# 17_USB_3_0.net
KiCad netlist of a schematic drawn in Altium Designer
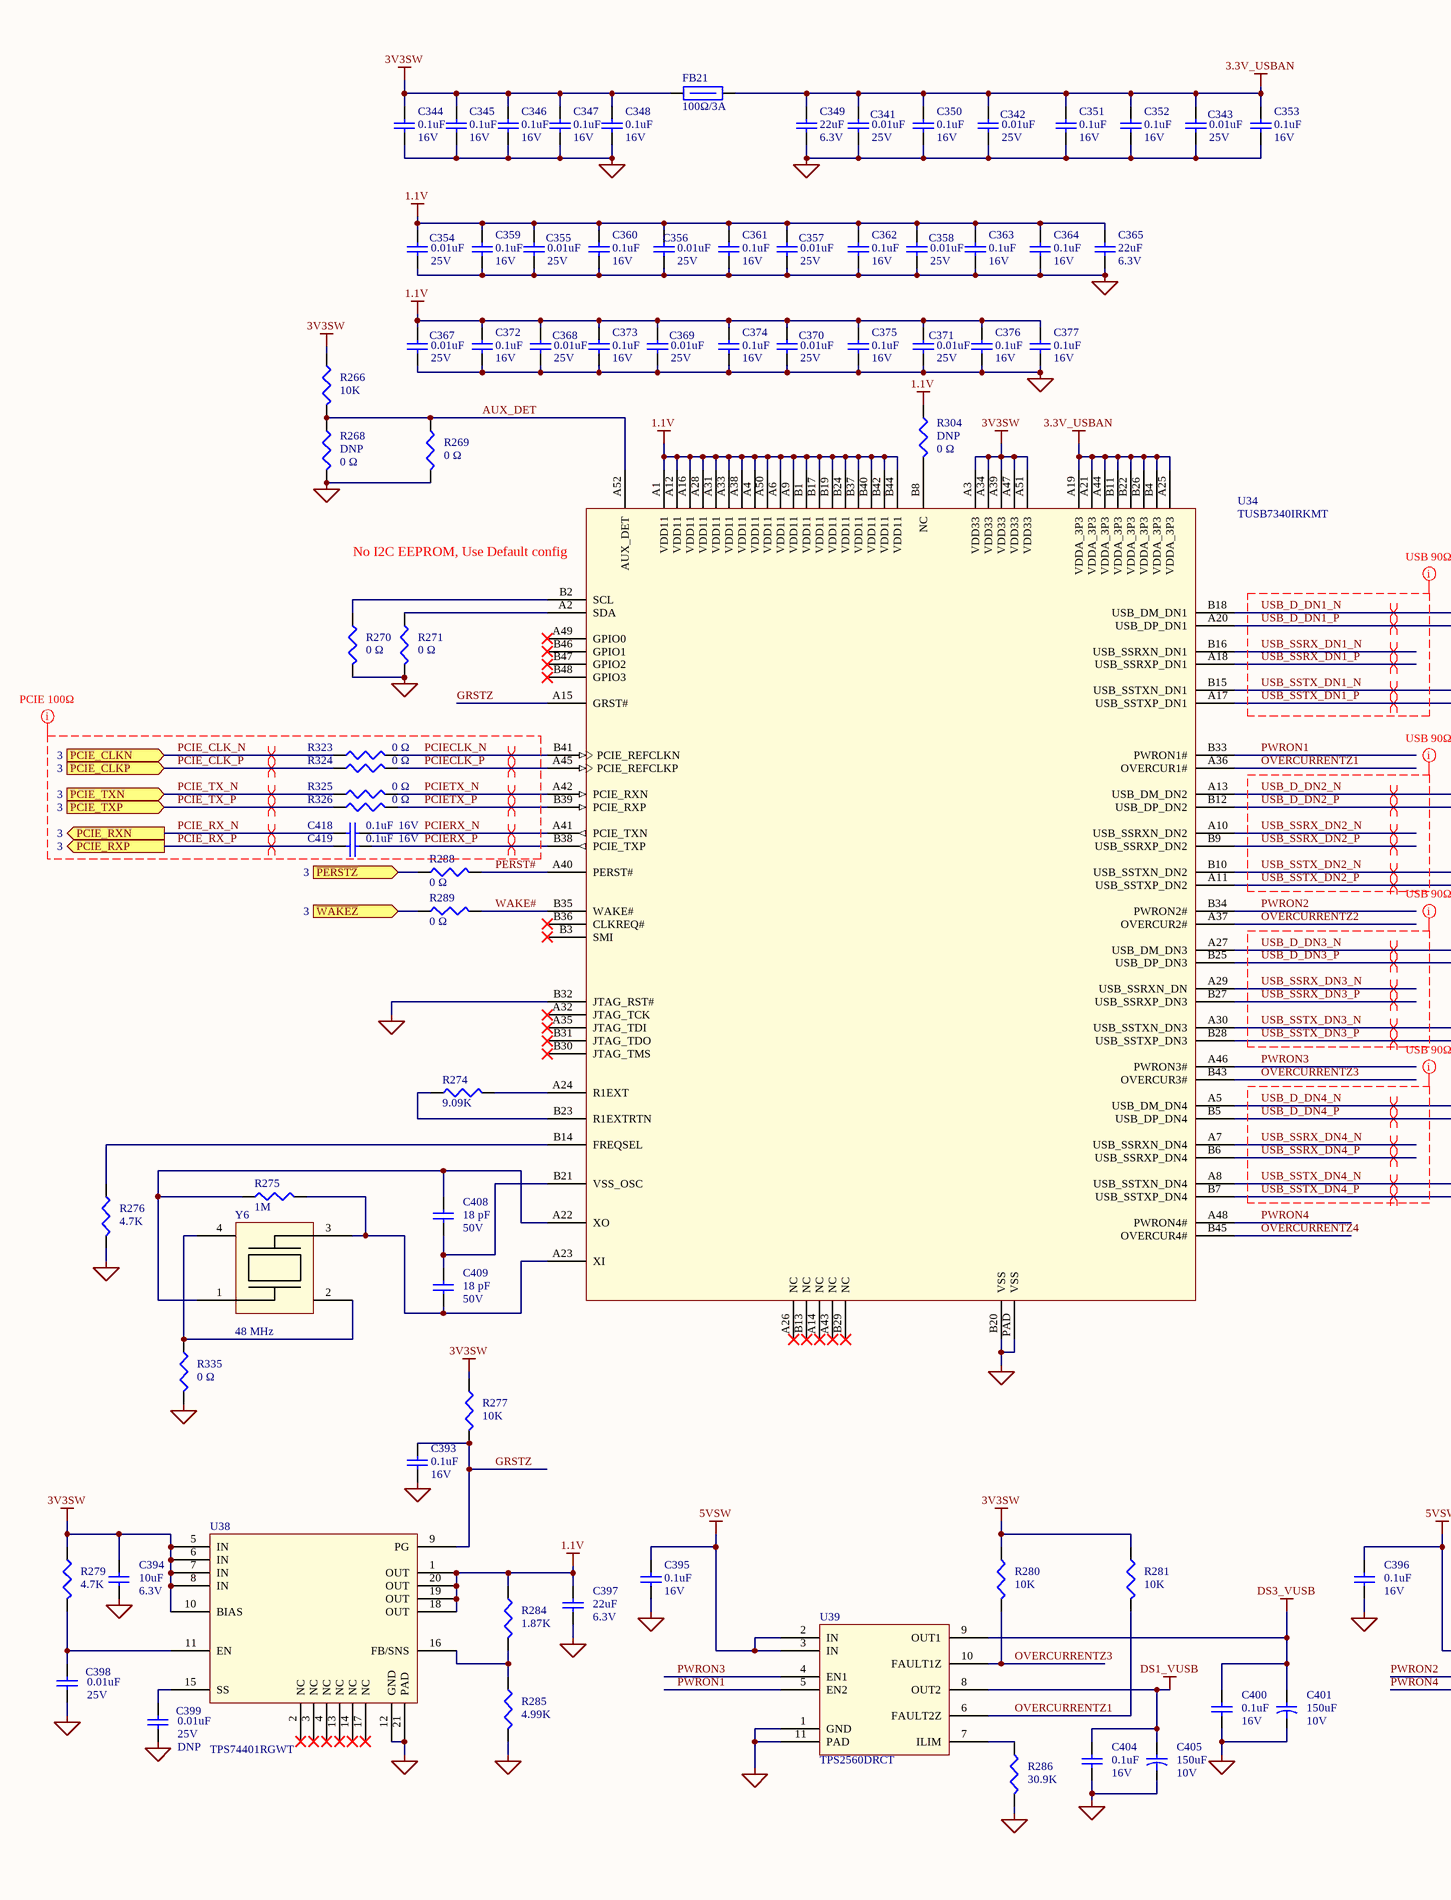
[diagram p0: 17 USB 3.0.SchDoc, left]
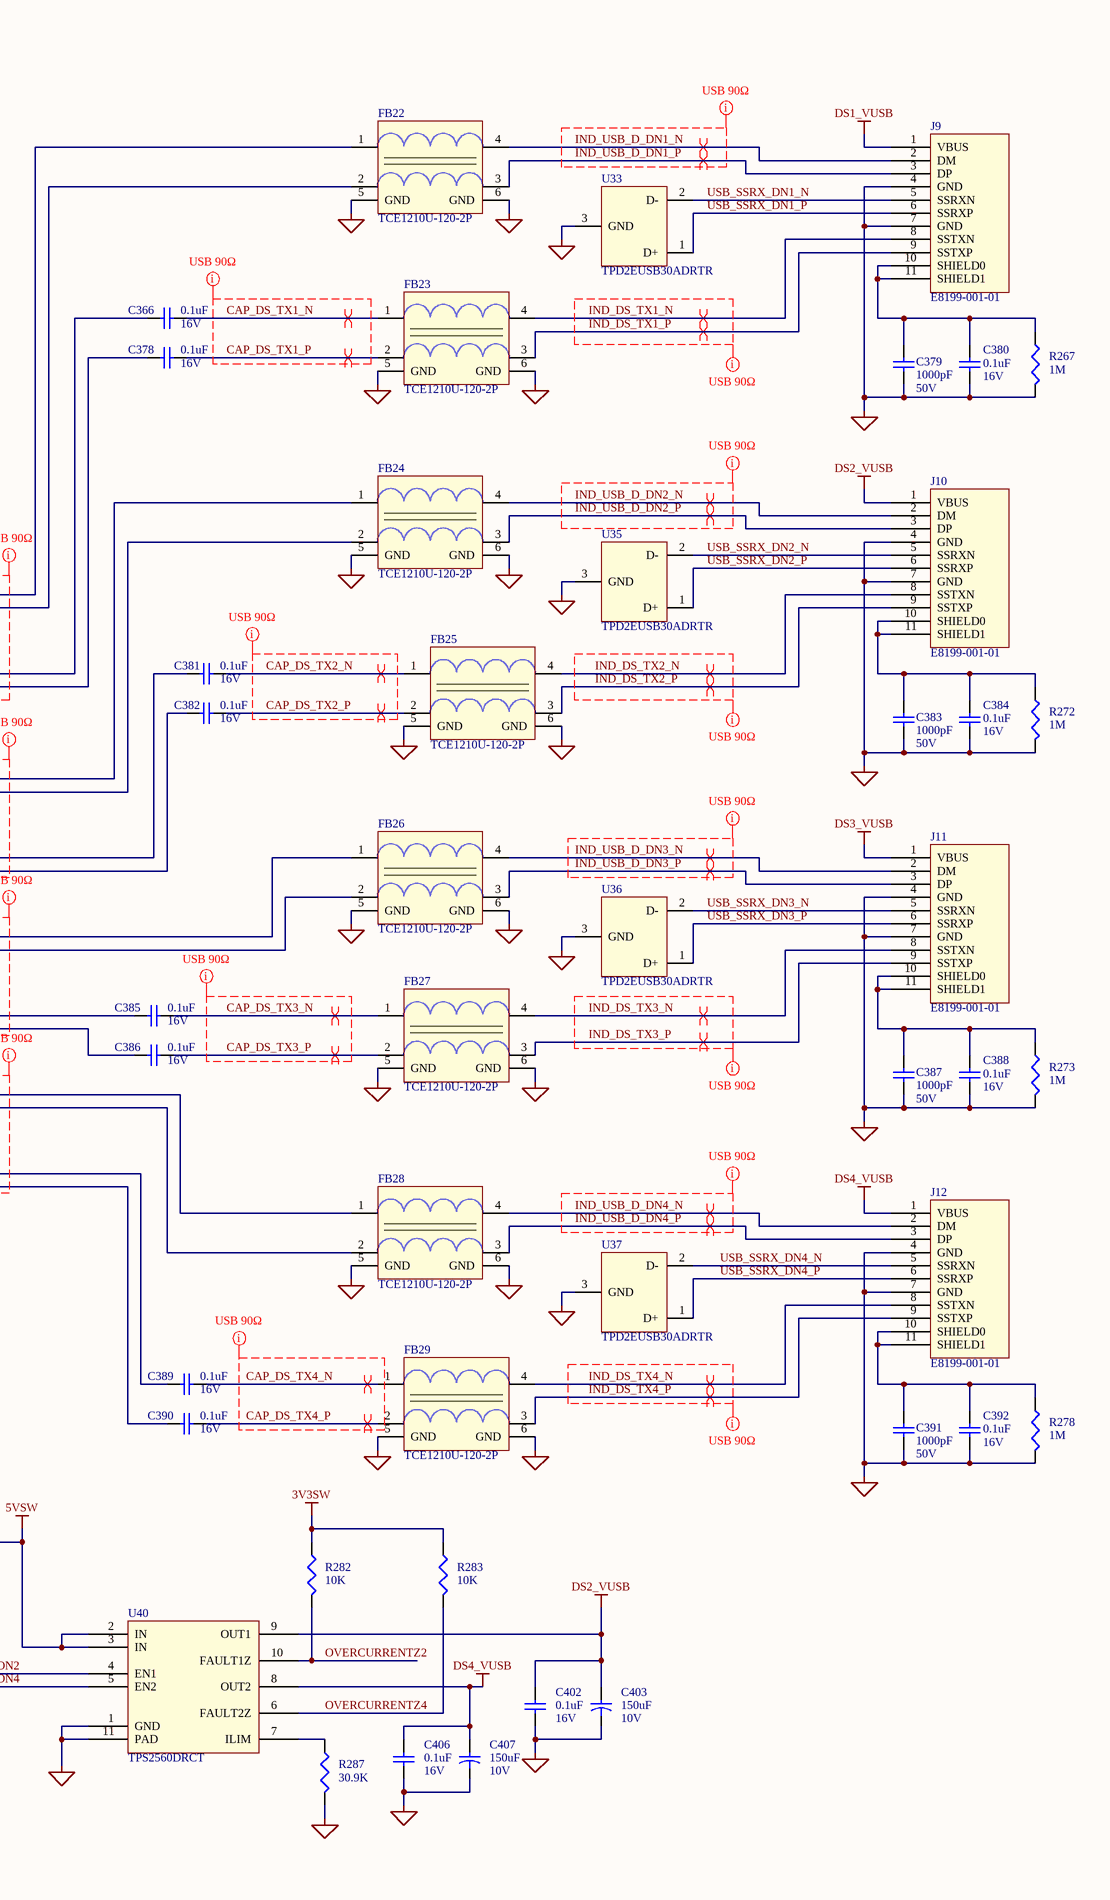
[diagram p1: 17 USB 3.0.SchDoc, right]

(export (version "E")
  (design (tool "Eeschema 10.0.6"))
  (components
    (comp (ref "C341")
      (value "0.01uF")
      (footprint "CAP_0402")
      (description "Cap, Cer, 0.01uF, 25V, ±10%, X7R, 0402")
      (fields
        (field (name "TOLERANCE") "±10%")
        (field (name "MANUFACTURER") "Murata")
        (field (name "VOLTAGE") "25V")
      )
      (libsource (lib "Firstview") (part "Cap 0.01uF 50V 0402"))
    )
    (comp (ref "C342")
      (value "0.01uF")
      (footprint "CAP_0402")
      (description "Cap, Cer, 0.01uF, 25V, ±10%, X7R, 0402")
      (fields
        (field (name "TOLERANCE") "±10%")
        (field (name "MANUFACTURER") "Murata")
        (field (name "VOLTAGE") "25V")
      )
      (libsource (lib "Firstview") (part "Cap 0.01uF 50V 0402"))
    )
    (comp (ref "C343")
      (value "0.01uF")
      (footprint "CAP_0402")
      (description "Cap, Cer, 0.01uF, 25V, ±10%, X7R, 0402")
      (fields
        (field (name "TOLERANCE") "±10%")
        (field (name "MANUFACTURER") "Murata")
        (field (name "VOLTAGE") "25V")
      )
      (libsource (lib "Firstview") (part "Cap 0.01uF 50V 0402"))
    )
    (comp (ref "C344")
      (value "0.1uF")
      (footprint "CAP_0402")
      (description "Cap, Cer, 0.1uF, 16V, 10%, X7R, 0402")
      (fields
        (field (name "TOLERANCE") "±10%")
        (field (name "MANUFACTURER") "Murata Electronics North America")
        (field (name "VOLTAGE") "16V")
      )
      (libsource (lib "Firstview") (part "Cap 0.1uF 16V 0402"))
    )
    (comp (ref "C345")
      (value "0.1uF")
      (footprint "CAP_0402")
      (description "Cap, Cer, 0.1uF, 16V, 10%, X7R, 0402")
      (fields
        (field (name "TOLERANCE") "±10%")
        (field (name "MANUFACTURER") "Murata Electronics North America")
        (field (name "VOLTAGE") "16V")
      )
      (libsource (lib "Firstview") (part "Cap 0.1uF 16V 0402"))
    )
    (comp (ref "C346")
      (value "0.1uF")
      (footprint "CAP_0402")
      (description "Cap, Cer, 0.1uF, 16V, 10%, X7R, 0402")
      (fields
        (field (name "TOLERANCE") "±10%")
        (field (name "MANUFACTURER") "Murata Electronics North America")
        (field (name "VOLTAGE") "16V")
      )
      (libsource (lib "Firstview") (part "Cap 0.1uF 16V 0402"))
    )
    (comp (ref "C347")
      (value "0.1uF")
      (footprint "CAP_0402")
      (description "Cap, Cer, 0.1uF, 16V, 10%, X7R, 0402")
      (fields
        (field (name "TOLERANCE") "±10%")
        (field (name "MANUFACTURER") "Murata Electronics North America")
        (field (name "VOLTAGE") "16V")
      )
      (libsource (lib "Firstview") (part "Cap 0.1uF 16V 0402"))
    )
    (comp (ref "C348")
      (value "0.1uF")
      (footprint "CAP_0402")
      (description "Cap, Cer, 0.1uF, 16V, 10%, X7R, 0402")
      (fields
        (field (name "TOLERANCE") "±10%")
        (field (name "MANUFACTURER") "Murata Electronics North America")
        (field (name "VOLTAGE") "16V")
      )
      (libsource (lib "Firstview") (part "Cap 0.1uF 16V 0402"))
    )
    (comp (ref "C349")
      (value "22uF")
      (footprint "CAP_0603")
      (description "Cap, Cer, 22uF, 6.3V, 20%, X5R, 0603")
      (fields
        (field (name "MANUFACTURER") "Murata Electronics North America")
        (field (name "TOLERANCE") "±10%")
        (field (name "VOLTAGE") "6.3V")
      )
      (libsource (lib "Firstview") (part "Cap 22uF 6.3V 0603"))
    )
    (comp (ref "C350")
      (value "0.1uF")
      (footprint "CAP_0402")
      (description "Cap, Cer, 0.1uF, 16V, 10%, X7R, 0402")
      (fields
        (field (name "TOLERANCE") "±10%")
        (field (name "MANUFACTURER") "Murata Electronics North America")
        (field (name "VOLTAGE") "16V")
      )
      (libsource (lib "Firstview") (part "Cap 0.1uF 16V 0402"))
    )
    (comp (ref "C351")
      (value "0.1uF")
      (footprint "CAP_0402")
      (description "Cap, Cer, 0.1uF, 16V, 10%, X7R, 0402")
      (fields
        (field (name "TOLERANCE") "±10%")
        (field (name "MANUFACTURER") "Murata Electronics North America")
        (field (name "VOLTAGE") "16V")
      )
      (libsource (lib "Firstview") (part "Cap 0.1uF 16V 0402"))
    )
    (comp (ref "C352")
      (value "0.1uF")
      (footprint "CAP_0402")
      (description "Cap, Cer, 0.1uF, 16V, 10%, X7R, 0402")
      (fields
        (field (name "TOLERANCE") "±10%")
        (field (name "MANUFACTURER") "Murata Electronics North America")
        (field (name "VOLTAGE") "16V")
      )
      (libsource (lib "Firstview") (part "Cap 0.1uF 16V 0402"))
    )
    (comp (ref "C353")
      (value "0.1uF")
      (footprint "CAP_0402")
      (description "Cap, Cer, 0.1uF, 16V, 10%, X7R, 0402")
      (fields
        (field (name "TOLERANCE") "±10%")
        (field (name "MANUFACTURER") "Murata Electronics North America")
        (field (name "VOLTAGE") "16V")
      )
      (libsource (lib "Firstview") (part "Cap 0.1uF 16V 0402"))
    )
    (comp (ref "C354")
      (value "0.01uF")
      (footprint "CAP_0402")
      (description "Cap, Cer, 0.01uF, 25V, ±10%, X7R, 0402")
      (fields
        (field (name "TOLERANCE") "±10%")
        (field (name "MANUFACTURER") "Murata")
        (field (name "VOLTAGE") "25V")
      )
      (libsource (lib "Firstview") (part "Cap 0.01uF 50V 0402"))
    )
    (comp (ref "C355")
      (value "0.01uF")
      (footprint "CAP_0402")
      (description "Cap, Cer, 0.01uF, 25V, ±10%, X7R, 0402")
      (fields
        (field (name "TOLERANCE") "±10%")
        (field (name "MANUFACTURER") "Murata")
        (field (name "VOLTAGE") "25V")
      )
      (libsource (lib "Firstview") (part "Cap 0.01uF 50V 0402"))
    )
    (comp (ref "C356")
      (value "0.01uF")
      (footprint "CAP_0402")
      (description "Cap, Cer, 0.01uF, 25V, ±10%, X7R, 0402")
      (fields
        (field (name "TOLERANCE") "±10%")
        (field (name "MANUFACTURER") "Murata")
        (field (name "VOLTAGE") "25V")
      )
      (libsource (lib "Firstview") (part "Cap 0.01uF 50V 0402"))
    )
    (comp (ref "C357")
      (value "0.01uF")
      (footprint "CAP_0402")
      (description "Cap, Cer, 0.01uF, 25V, ±10%, X7R, 0402")
      (fields
        (field (name "TOLERANCE") "±10%")
        (field (name "MANUFACTURER") "Murata")
        (field (name "VOLTAGE") "25V")
      )
      (libsource (lib "Firstview") (part "Cap 0.01uF 50V 0402"))
    )
    (comp (ref "C358")
      (value "0.01uF")
      (footprint "CAP_0402")
      (description "Cap, Cer, 0.01uF, 25V, ±10%, X7R, 0402")
      (fields
        (field (name "TOLERANCE") "±10%")
        (field (name "MANUFACTURER") "Murata")
        (field (name "VOLTAGE") "25V")
      )
      (libsource (lib "Firstview") (part "Cap 0.01uF 50V 0402"))
    )
    (comp (ref "C359")
      (value "0.1uF")
      (footprint "CAP_0402")
      (description "Cap, Cer, 0.1uF, 16V, 10%, X7R, 0402")
      (fields
        (field (name "TOLERANCE") "±10%")
        (field (name "MANUFACTURER") "Murata Electronics North America")
        (field (name "VOLTAGE") "16V")
      )
      (libsource (lib "Firstview") (part "Cap 0.1uF 16V 0402"))
    )
    (comp (ref "C360")
      (value "0.1uF")
      (footprint "CAP_0402")
      (description "Cap, Cer, 0.1uF, 16V, 10%, X7R, 0402")
      (fields
        (field (name "TOLERANCE") "±10%")
        (field (name "MANUFACTURER") "Murata Electronics North America")
        (field (name "VOLTAGE") "16V")
      )
      (libsource (lib "Firstview") (part "Cap 0.1uF 16V 0402"))
    )
    (comp (ref "C361")
      (value "0.1uF")
      (footprint "CAP_0402")
      (description "Cap, Cer, 0.1uF, 16V, 10%, X7R, 0402")
      (fields
        (field (name "TOLERANCE") "±10%")
        (field (name "MANUFACTURER") "Murata Electronics North America")
        (field (name "VOLTAGE") "16V")
      )
      (libsource (lib "Firstview") (part "Cap 0.1uF 16V 0402"))
    )
    (comp (ref "C362")
      (value "0.1uF")
      (footprint "CAP_0402")
      (description "Cap, Cer, 0.1uF, 16V, 10%, X7R, 0402")
      (fields
        (field (name "TOLERANCE") "±10%")
        (field (name "MANUFACTURER") "Murata Electronics North America")
        (field (name "VOLTAGE") "16V")
      )
      (libsource (lib "Firstview") (part "Cap 0.1uF 16V 0402"))
    )
    (comp (ref "C363")
      (value "0.1uF")
      (footprint "CAP_0402")
      (description "Cap, Cer, 0.1uF, 16V, 10%, X7R, 0402")
      (fields
        (field (name "TOLERANCE") "±10%")
        (field (name "MANUFACTURER") "Murata Electronics North America")
        (field (name "VOLTAGE") "16V")
      )
      (libsource (lib "Firstview") (part "Cap 0.1uF 16V 0402"))
    )
    (comp (ref "C364")
      (value "0.1uF")
      (footprint "CAP_0402")
      (description "Cap, Cer, 0.1uF, 16V, 10%, X7R, 0402")
      (fields
        (field (name "TOLERANCE") "±10%")
        (field (name "MANUFACTURER") "Murata Electronics North America")
        (field (name "VOLTAGE") "16V")
      )
      (libsource (lib "Firstview") (part "Cap 0.1uF 16V 0402"))
    )
    (comp (ref "C365")
      (value "22uF")
      (footprint "CAP_0603")
      (description "Cap, Cer, 22uF, 6.3V, 20%, X5R, 0603")
      (fields
        (field (name "MANUFACTURER") "Murata Electronics North America")
        (field (name "TOLERANCE") "±10%")
        (field (name "VOLTAGE") "6.3V")
      )
      (libsource (lib "Firstview") (part "Cap 22uF 6.3V 0603"))
    )
    (comp (ref "C366")
      (value "0.1uF")
      (footprint "CAP_0402")
      (description "Cap, Cer, 0.1uF, 16V, 10%, X7R, 0402")
      (fields
        (field (name "TOLERANCE") "±10%")
        (field (name "MANUFACTURER") "Murata Electronics North America")
        (field (name "VOLTAGE") "16V")
      )
      (libsource (lib "Firstview") (part "Cap 0.1uF 16V 0402"))
    )
    (comp (ref "C367")
      (value "0.01uF")
      (footprint "CAP_0402")
      (description "Cap, Cer, 0.01uF, 25V, ±10%, X7R, 0402")
      (fields
        (field (name "TOLERANCE") "±10%")
        (field (name "MANUFACTURER") "Murata")
        (field (name "VOLTAGE") "25V")
      )
      (libsource (lib "Firstview") (part "Cap 0.01uF 50V 0402"))
    )
    (comp (ref "C368")
      (value "0.01uF")
      (footprint "CAP_0402")
      (description "Cap, Cer, 0.01uF, 25V, ±10%, X7R, 0402")
      (fields
        (field (name "TOLERANCE") "±10%")
        (field (name "MANUFACTURER") "Murata")
        (field (name "VOLTAGE") "25V")
      )
      (libsource (lib "Firstview") (part "Cap 0.01uF 50V 0402"))
    )
    (comp (ref "C369")
      (value "0.01uF")
      (footprint "CAP_0402")
      (description "Cap, Cer, 0.01uF, 25V, ±10%, X7R, 0402")
      (fields
        (field (name "TOLERANCE") "±10%")
        (field (name "MANUFACTURER") "Murata")
        (field (name "VOLTAGE") "25V")
      )
      (libsource (lib "Firstview") (part "Cap 0.01uF 50V 0402"))
    )
    (comp (ref "C370")
      (value "0.01uF")
      (footprint "CAP_0402")
      (description "Cap, Cer, 0.01uF, 25V, ±10%, X7R, 0402")
      (fields
        (field (name "TOLERANCE") "±10%")
        (field (name "MANUFACTURER") "Murata")
        (field (name "VOLTAGE") "25V")
      )
      (libsource (lib "Firstview") (part "Cap 0.01uF 50V 0402"))
    )
    (comp (ref "C371")
      (value "0.01uF")
      (footprint "CAP_0402")
      (description "Cap, Cer, 0.01uF, 25V, ±10%, X7R, 0402")
      (fields
        (field (name "TOLERANCE") "±10%")
        (field (name "MANUFACTURER") "Murata")
        (field (name "VOLTAGE") "25V")
      )
      (libsource (lib "Firstview") (part "Cap 0.01uF 50V 0402"))
    )
    (comp (ref "C372")
      (value "0.1uF")
      (footprint "CAP_0402")
      (description "Cap, Cer, 0.1uF, 16V, 10%, X7R, 0402")
      (fields
        (field (name "TOLERANCE") "±10%")
        (field (name "MANUFACTURER") "Murata Electronics North America")
        (field (name "VOLTAGE") "16V")
      )
      (libsource (lib "Firstview") (part "Cap 0.1uF 16V 0402"))
    )
    (comp (ref "C373")
      (value "0.1uF")
      (footprint "CAP_0402")
      (description "Cap, Cer, 0.1uF, 16V, 10%, X7R, 0402")
      (fields
        (field (name "TOLERANCE") "±10%")
        (field (name "MANUFACTURER") "Murata Electronics North America")
        (field (name "VOLTAGE") "16V")
      )
      (libsource (lib "Firstview") (part "Cap 0.1uF 16V 0402"))
    )
    (comp (ref "C374")
      (value "0.1uF")
      (footprint "CAP_0402")
      (description "Cap, Cer, 0.1uF, 16V, 10%, X7R, 0402")
      (fields
        (field (name "TOLERANCE") "±10%")
        (field (name "MANUFACTURER") "Murata Electronics North America")
        (field (name "VOLTAGE") "16V")
      )
      (libsource (lib "Firstview") (part "Cap 0.1uF 16V 0402"))
    )
    (comp (ref "C375")
      (value "0.1uF")
      (footprint "CAP_0402")
      (description "Cap, Cer, 0.1uF, 16V, 10%, X7R, 0402")
      (fields
        (field (name "TOLERANCE") "±10%")
        (field (name "MANUFACTURER") "Murata Electronics North America")
        (field (name "VOLTAGE") "16V")
      )
      (libsource (lib "Firstview") (part "Cap 0.1uF 16V 0402"))
    )
    (comp (ref "C376")
      (value "0.1uF")
      (footprint "CAP_0402")
      (description "Cap, Cer, 0.1uF, 16V, 10%, X7R, 0402")
      (fields
        (field (name "TOLERANCE") "±10%")
        (field (name "MANUFACTURER") "Murata Electronics North America")
        (field (name "VOLTAGE") "16V")
      )
      (libsource (lib "Firstview") (part "Cap 0.1uF 16V 0402"))
    )
    (comp (ref "C377")
      (value "0.1uF")
      (footprint "CAP_0402")
      (description "Cap, Cer, 0.1uF, 16V, 10%, X7R, 0402")
      (fields
        (field (name "TOLERANCE") "±10%")
        (field (name "MANUFACTURER") "Murata Electronics North America")
        (field (name "VOLTAGE") "16V")
      )
      (libsource (lib "Firstview") (part "Cap 0.1uF 16V 0402"))
    )
    (comp (ref "C378")
      (value "0.1uF")
      (footprint "CAP_0402")
      (description "Cap, Cer, 0.1uF, 16V, 10%, X7R, 0402")
      (fields
        (field (name "TOLERANCE") "±10%")
        (field (name "MANUFACTURER") "Murata Electronics North America")
        (field (name "VOLTAGE") "16V")
      )
      (libsource (lib "Firstview") (part "Cap 0.1uF 16V 0402"))
    )
    (comp (ref "C379")
      (value "1000pF")
      (footprint "CAP_0402")
      (description "Cap, Cer, 1000pF, 50V, 20%, X7R, 0402")
      (fields
        (field (name "TOLERANCE") "20%")
        (field (name "MANUFACTURER") "Murata Electronics North America")
        (field (name "VOLTAGE") "50V")
      )
      (libsource (lib "Firstview") (part "Cap 1000pF 50V 0402"))
    )
    (comp (ref "C380")
      (value "0.1uF")
      (footprint "CAP_0402")
      (description "Cap, Cer, 0.1uF, 16V, 10%, X7R, 0402")
      (fields
        (field (name "TOLERANCE") "±10%")
        (field (name "MANUFACTURER") "Murata Electronics North America")
        (field (name "VOLTAGE") "16V")
      )
      (libsource (lib "Firstview") (part "Cap 0.1uF 16V 0402"))
    )
    (comp (ref "C381")
      (value "0.1uF")
      (footprint "CAP_0402")
      (description "Cap, Cer, 0.1uF, 16V, 10%, X7R, 0402")
      (fields
        (field (name "TOLERANCE") "±10%")
        (field (name "MANUFACTURER") "Murata Electronics North America")
        (field (name "VOLTAGE") "16V")
      )
      (libsource (lib "Firstview") (part "Cap 0.1uF 16V 0402"))
    )
    (comp (ref "C382")
      (value "0.1uF")
      (footprint "CAP_0402")
      (description "Cap, Cer, 0.1uF, 16V, 10%, X7R, 0402")
      (fields
        (field (name "TOLERANCE") "±10%")
        (field (name "MANUFACTURER") "Murata Electronics North America")
        (field (name "VOLTAGE") "16V")
      )
      (libsource (lib "Firstview") (part "Cap 0.1uF 16V 0402"))
    )
    (comp (ref "C383")
      (value "1000pF")
      (footprint "CAP_0402")
      (description "Cap, Cer, 1000pF, 50V, 20%, X7R, 0402")
      (fields
        (field (name "TOLERANCE") "20%")
        (field (name "MANUFACTURER") "Murata Electronics North America")
        (field (name "VOLTAGE") "50V")
      )
      (libsource (lib "Firstview") (part "Cap 1000pF 50V 0402"))
    )
    (comp (ref "C384")
      (value "0.1uF")
      (footprint "CAP_0402")
      (description "Cap, Cer, 0.1uF, 16V, 10%, X7R, 0402")
      (fields
        (field (name "TOLERANCE") "±10%")
        (field (name "MANUFACTURER") "Murata Electronics North America")
        (field (name "VOLTAGE") "16V")
      )
      (libsource (lib "Firstview") (part "Cap 0.1uF 16V 0402"))
    )
    (comp (ref "C385")
      (value "0.1uF")
      (footprint "CAP_0402")
      (description "Cap, Cer, 0.1uF, 16V, 10%, X7R, 0402")
      (fields
        (field (name "TOLERANCE") "±10%")
        (field (name "MANUFACTURER") "Murata Electronics North America")
        (field (name "VOLTAGE") "16V")
      )
      (libsource (lib "Firstview") (part "Cap 0.1uF 16V 0402"))
    )
    (comp (ref "C386")
      (value "0.1uF")
      (footprint "CAP_0402")
      (description "Cap, Cer, 0.1uF, 16V, 10%, X7R, 0402")
      (fields
        (field (name "TOLERANCE") "±10%")
        (field (name "MANUFACTURER") "Murata Electronics North America")
        (field (name "VOLTAGE") "16V")
      )
      (libsource (lib "Firstview") (part "Cap 0.1uF 16V 0402"))
    )
    (comp (ref "C387")
      (value "1000pF")
      (footprint "CAP_0402")
      (description "Cap, Cer, 1000pF, 50V, 20%, X7R, 0402")
      (fields
        (field (name "TOLERANCE") "20%")
        (field (name "MANUFACTURER") "Murata Electronics North America")
        (field (name "VOLTAGE") "50V")
      )
      (libsource (lib "Firstview") (part "Cap 1000pF 50V 0402"))
    )
    (comp (ref "C388")
      (value "0.1uF")
      (footprint "CAP_0402")
      (description "Cap, Cer, 0.1uF, 16V, 10%, X7R, 0402")
      (fields
        (field (name "TOLERANCE") "±10%")
        (field (name "MANUFACTURER") "Murata Electronics North America")
        (field (name "VOLTAGE") "16V")
      )
      (libsource (lib "Firstview") (part "Cap 0.1uF 16V 0402"))
    )
    (comp (ref "C389")
      (value "0.1uF")
      (footprint "CAP_0402")
      (description "Cap, Cer, 0.1uF, 16V, 10%, X7R, 0402")
      (fields
        (field (name "TOLERANCE") "±10%")
        (field (name "MANUFACTURER") "Murata Electronics North America")
        (field (name "VOLTAGE") "16V")
      )
      (libsource (lib "Firstview") (part "Cap 0.1uF 16V 0402"))
    )
    (comp (ref "C390")
      (value "0.1uF")
      (footprint "CAP_0402")
      (description "Cap, Cer, 0.1uF, 16V, 10%, X7R, 0402")
      (fields
        (field (name "TOLERANCE") "±10%")
        (field (name "MANUFACTURER") "Murata Electronics North America")
        (field (name "VOLTAGE") "16V")
      )
      (libsource (lib "Firstview") (part "Cap 0.1uF 16V 0402"))
    )
    (comp (ref "C391")
      (value "1000pF")
      (footprint "CAP_0402")
      (description "Cap, Cer, 1000pF, 50V, 20%, X7R, 0402")
      (fields
        (field (name "TOLERANCE") "20%")
        (field (name "MANUFACTURER") "Murata Electronics North America")
        (field (name "VOLTAGE") "50V")
      )
      (libsource (lib "Firstview") (part "Cap 1000pF 50V 0402"))
    )
    (comp (ref "C392")
      (value "0.1uF")
      (footprint "CAP_0402")
      (description "Cap, Cer, 0.1uF, 16V, 10%, X7R, 0402")
      (fields
        (field (name "TOLERANCE") "±10%")
        (field (name "MANUFACTURER") "Murata Electronics North America")
        (field (name "VOLTAGE") "16V")
      )
      (libsource (lib "Firstview") (part "Cap 0.1uF 16V 0402"))
    )
    (comp (ref "C393")
      (value "0.1uF")
      (footprint "CAP_0402")
      (description "Cap, Cer, 0.1uF, 16V, 10%, X7R, 0402")
      (fields
        (field (name "TOLERANCE") "±10%")
        (field (name "MANUFACTURER") "Murata Electronics North America")
        (field (name "VOLTAGE") "16V")
      )
      (libsource (lib "Firstview") (part "Cap 0.1uF 16V 0402"))
    )
    (comp (ref "C394")
      (value "10uF")
      (footprint "CAP_0402")
      (description "Cap, Cer, 10uF, 6.3V, 20%, X5R, 0402")
      (fields
        (field (name "TOLERANCE") "±20%")
        (field (name "MANUFACTURER") "Samsung Electro-Mechanics America, Inc")
        (field (name "VOLTAGE") "6.3V")
      )
      (libsource (lib "Firstview") (part "Cap 10uF 6.3V 0402"))
    )
    (comp (ref "C395")
      (value "0.1uF")
      (footprint "CAP_0402")
      (description "Cap, Cer, 0.1uF, 16V, 10%, X7R, 0402")
      (fields
        (field (name "TOLERANCE") "±10%")
        (field (name "MANUFACTURER") "Murata Electronics North America")
        (field (name "VOLTAGE") "16V")
      )
      (libsource (lib "Firstview") (part "Cap 0.1uF 16V 0402"))
    )
    (comp (ref "C396")
      (value "0.1uF")
      (footprint "CAP_0402")
      (description "Cap, Cer, 0.1uF, 16V, 10%, X7R, 0402")
      (fields
        (field (name "TOLERANCE") "±10%")
        (field (name "MANUFACTURER") "Murata Electronics North America")
        (field (name "VOLTAGE") "16V")
      )
      (libsource (lib "Firstview") (part "Cap 0.1uF 16V 0402"))
    )
    (comp (ref "C397")
      (value "22uF")
      (footprint "CAP_0603")
      (description "Cap, Cer, 22uF, 6.3V, 20%, X5R, 0603")
      (fields
        (field (name "MANUFACTURER") "Murata Electronics North America")
        (field (name "TOLERANCE") "±10%")
        (field (name "VOLTAGE") "6.3V")
      )
      (libsource (lib "Firstview") (part "Cap 22uF 6.3V 0603"))
    )
    (comp (ref "C398")
      (value "0.01uF")
      (footprint "CAP_0402")
      (description "Cap, Cer, 0.01uF, 25V, ±10%, X7R, 0402")
      (fields
        (field (name "TOLERANCE") "±10%")
        (field (name "MANUFACTURER") "Murata")
        (field (name "VOLTAGE") "25V")
      )
      (libsource (lib "Firstview") (part "Cap 0.01uF 50V 0402"))
    )
    (comp (ref "C399")
      (value "0.01uF")
      (footprint "CAP_0402")
      (description "Cap, Cer, 0.01uF, 25V, ±10%, X7R, 0402")
      (fields
        (field (name "TOLERANCE") "±10%")
        (field (name "DNP") "DNP")
        (field (name "MANUFACTURER") "Murata")
        (field (name "VOLTAGE") "25V")
      )
      (libsource (lib "Firstview") (part "Cap 0.01uF 50V 0402"))
    )
    (comp (ref "C400")
      (value "0.1uF")
      (footprint "CAP_0402")
      (description "Cap, Cer, 0.1uF, 16V, 10%, X7R, 0402")
      (fields
        (field (name "TOLERANCE") "±10%")
        (field (name "MANUFACTURER") "Murata Electronics North America")
        (field (name "VOLTAGE") "16V")
      )
      (libsource (lib "Firstview") (part "Cap 0.1uF 16V 0402"))
    )
    (comp (ref "C401")
      (value "150uF")
      (footprint "SMD(6.6x6.6x5.8)_WT1A151MCL1GS")
      (description "Cap, Alum, 150µF, 10V, 20%, SMD")
      (fields
        (field (name "TOLERANCE") "20%")
        (field (name "MANUFACTURER") "Nichicon")
        (field (name "VOLTAGE") "10V")
      )
      (libsource (lib "Firstview") (part "Cap 150uF 10V"))
    )
    (comp (ref "C402")
      (value "0.1uF")
      (footprint "CAP_0402")
      (description "Cap, Cer, 0.1uF, 16V, 10%, X7R, 0402")
      (fields
        (field (name "TOLERANCE") "±10%")
        (field (name "MANUFACTURER") "Murata Electronics North America")
        (field (name "VOLTAGE") "16V")
      )
      (libsource (lib "Firstview") (part "Cap 0.1uF 16V 0402"))
    )
    (comp (ref "C403")
      (value "150uF")
      (footprint "SMD(6.6x6.6x5.8)_WT1A151MCL1GS")
      (description "Cap, Alum, 150µF, 10V, 20%, SMD")
      (fields
        (field (name "TOLERANCE") "20%")
        (field (name "MANUFACTURER") "Nichicon")
        (field (name "VOLTAGE") "10V")
      )
      (libsource (lib "Firstview") (part "Cap 150uF 10V"))
    )
    (comp (ref "C404")
      (value "0.1uF")
      (footprint "CAP_0402")
      (description "Cap, Cer, 0.1uF, 16V, 10%, X7R, 0402")
      (fields
        (field (name "TOLERANCE") "±10%")
        (field (name "MANUFACTURER") "Murata Electronics North America")
        (field (name "VOLTAGE") "16V")
      )
      (libsource (lib "Firstview") (part "Cap 0.1uF 16V 0402"))
    )
    (comp (ref "C405")
      (value "150uF")
      (footprint "SMD(6.6x6.6x5.8)_WT1A151MCL1GS")
      (description "Cap, Alum, 150µF, 10V, 20%, SMD")
      (fields
        (field (name "TOLERANCE") "20%")
        (field (name "MANUFACTURER") "Nichicon")
        (field (name "VOLTAGE") "10V")
      )
      (libsource (lib "Firstview") (part "Cap 150uF 10V"))
    )
    (comp (ref "C406")
      (value "0.1uF")
      (footprint "CAP_0402")
      (description "Cap, Cer, 0.1uF, 16V, 10%, X7R, 0402")
      (fields
        (field (name "TOLERANCE") "±10%")
        (field (name "MANUFACTURER") "Murata Electronics North America")
        (field (name "VOLTAGE") "16V")
      )
      (libsource (lib "Firstview") (part "Cap 0.1uF 16V 0402"))
    )
    (comp (ref "C407")
      (value "150uF")
      (footprint "SMD(6.6x6.6x5.8)_WT1A151MCL1GS")
      (description "Cap, Alum, 150µF, 10V, 20%, SMD")
      (fields
        (field (name "TOLERANCE") "20%")
        (field (name "MANUFACTURER") "Nichicon")
        (field (name "VOLTAGE") "10V")
      )
      (libsource (lib "Firstview") (part "Cap 150uF 10V"))
    )
    (comp (ref "C408")
      (value "18 pF")
      (footprint "CAP_0402")
      (description "Cap, Cer, 18pF, 50V, 5%, C0G, 0402")
      (fields
        (field (name "MANUFACTURER") "TDK Corporation")
        (field (name "VOLTAGE") "50V")
        (field (name "Comment") "Cap 18pF 50V 0402")
      )
      (libsource (lib "Firstview") (part "Cap 18pF 50V 0402"))
    )
    (comp (ref "C409")
      (value "18 pF")
      (footprint "CAP_0402")
      (description "Cap, Cer, 18pF, 50V, 5%, C0G, 0402")
      (fields
        (field (name "MANUFACTURER") "TDK Corporation")
        (field (name "VOLTAGE") "50V")
        (field (name "Comment") "Cap 18pF 50V 0402")
      )
      (libsource (lib "Firstview") (part "Cap 18pF 50V 0402"))
    )
    (comp (ref "C418")
      (value "0.1uF")
      (footprint "CAP_0402")
      (description "Cap, Cer, 0.1uF, 16V, 10%, X7R, 0402")
      (fields
        (field (name "TOLERANCE") "±10%")
        (field (name "MANUFACTURER") "Murata Electronics North America")
        (field (name "VOLTAGE") "16V")
      )
      (libsource (lib "Firstview") (part "Cap 0.1uF 16V 0402"))
    )
    (comp (ref "C419")
      (value "0.1uF")
      (footprint "CAP_0402")
      (description "Cap, Cer, 0.1uF, 16V, 10%, X7R, 0402")
      (fields
        (field (name "TOLERANCE") "±10%")
        (field (name "MANUFACTURER") "Murata Electronics North America")
        (field (name "VOLTAGE") "16V")
      )
      (libsource (lib "Firstview") (part "Cap 0.1uF 16V 0402"))
    )
    (comp (ref "FB21")
      (value "100Ω/3A")
      (footprint "IND_0603")
      (description "Ind, Ferrite Bead, 100R, 30mOhm, 3A, 0603")
      (fields
        (field (name "MANUFACTURER") "Murata Electronics North America")
        (field (name "Comment") "BLM18KG101TN1D")
      )
      (libsource (lib "Firstview") (part "BLM18KG101TN1D"))
    )
    (comp (ref "FB22")
      (value "TCE1210U-120-2P")
      (footprint "USB_TCE1210U-120-2P")
      (description "Choke, Common Mode, 12 ohm, SMD")
      (fields (field (name "MANUFACTURER") "TDK Corporation"))
      (libsource (lib "Firstview") (part "TCE1210U-120-2P"))
    )
    (comp (ref "FB23")
      (value "TCE1210U-120-2P")
      (footprint "USB_TCE1210U-120-2P")
      (description "Choke, Common Mode, 12 ohm, SMD")
      (fields (field (name "MANUFACTURER") "TDK Corporation"))
      (libsource (lib "Firstview") (part "TCE1210U-120-2P"))
    )
    (comp (ref "FB24")
      (value "TCE1210U-120-2P")
      (footprint "USB_TCE1210U-120-2P")
      (description "Choke, Common Mode, 12 ohm, SMD")
      (fields (field (name "MANUFACTURER") "TDK Corporation"))
      (libsource (lib "Firstview") (part "TCE1210U-120-2P"))
    )
    (comp (ref "FB25")
      (value "TCE1210U-120-2P")
      (footprint "USB_TCE1210U-120-2P")
      (description "Choke, Common Mode, 12 ohm, SMD")
      (fields (field (name "MANUFACTURER") "TDK Corporation"))
      (libsource (lib "Firstview") (part "TCE1210U-120-2P"))
    )
    (comp (ref "FB26")
      (value "TCE1210U-120-2P")
      (footprint "USB_TCE1210U-120-2P")
      (description "Choke, Common Mode, 12 ohm, SMD")
      (fields (field (name "MANUFACTURER") "TDK Corporation"))
      (libsource (lib "Firstview") (part "TCE1210U-120-2P"))
    )
    (comp (ref "FB27")
      (value "TCE1210U-120-2P")
      (footprint "USB_TCE1210U-120-2P")
      (description "Choke, Common Mode, 12 ohm, SMD")
      (fields (field (name "MANUFACTURER") "TDK Corporation"))
      (libsource (lib "Firstview") (part "TCE1210U-120-2P"))
    )
    (comp (ref "FB28")
      (value "TCE1210U-120-2P")
      (footprint "USB_TCE1210U-120-2P")
      (description "Choke, Common Mode, 12 ohm, SMD")
      (fields (field (name "MANUFACTURER") "TDK Corporation"))
      (libsource (lib "Firstview") (part "TCE1210U-120-2P"))
    )
    (comp (ref "FB29")
      (value "TCE1210U-120-2P")
      (footprint "USB_TCE1210U-120-2P")
      (description "Choke, Common Mode, 12 ohm, SMD")
      (fields (field (name "MANUFACTURER") "TDK Corporation"))
      (libsource (lib "Firstview") (part "TCE1210U-120-2P"))
    )
    (comp (ref "J9")
      (value "E8199-001-01")
      (footprint "USB_E8199-001-01")
      (description "Conn, USB 3.0, TYPE A RCPT, TH")
      (fields (field (name "MANUFACTURER") "Pulse Electronics Corporation"))
      (libsource (lib "Firstview") (part "E8199-001-01"))
    )
    (comp (ref "J10")
      (value "E8199-001-01")
      (footprint "USB_E8199-001-01")
      (description "Conn, USB 3.0, TYPE A RCPT, TH")
      (fields (field (name "MANUFACTURER") "Pulse Electronics Corporation"))
      (libsource (lib "Firstview") (part "E8199-001-01"))
    )
    (comp (ref "J11")
      (value "E8199-001-01")
      (footprint "USB_E8199-001-01")
      (description "Conn, USB 3.0, TYPE A RCPT, TH")
      (fields (field (name "MANUFACTURER") "Pulse Electronics Corporation"))
      (libsource (lib "Firstview") (part "E8199-001-01"))
    )
    (comp (ref "J12")
      (value "E8199-001-01")
      (footprint "USB_E8199-001-01")
      (description "Conn, USB 3.0, TYPE A RCPT, TH")
      (fields (field (name "MANUFACTURER") "Pulse Electronics Corporation"))
      (libsource (lib "Firstview") (part "E8199-001-01"))
    )
    (comp (ref "R266")
      (value "10K")
      (footprint "RES_0402")
      (description "Res, 10K, 1/16W, 1%, 0402")
      (fields (field (name "MANUFACTURER") "Yageo") (field (name "Comment") "Res 10K 0.063W"))
      (libsource (lib "Firstview") (part "Res 10K 0.063W"))
    )
    (comp (ref "R267")
      (value "1M")
      (footprint "RES_0402")
      (description "Res, 1M, 0.063W, 1%, 0402")
      (fields (field (name "MANUFACTURER") "Yageo") (field (name "Comment") "Res 1M 0.063W"))
      (libsource (lib "Firstview") (part "Res 1M 0.063W"))
    )
    (comp (ref "R268")
      (value "0 Ω")
      (footprint "RES_0402")
      (description "Res, 0 ohm, 1/16W, 0402")
      (fields
        (field (name "MANUFACTURER") "Vishay Dale")
        (field (name "DNP") "DNP")
        (field (name "Comment") "Res 0 ohm 0.1W DNP")
      )
      (libsource (lib "Firstview") (part "Res 0 ohm 0.1W DNP"))
    )
    (comp (ref "R269")
      (value "0 Ω")
      (footprint "RES_0402")
      (description "Res, 0 ohm, 1/16W, 0402")
      (fields (field (name "MANUFACTURER") "Vishay Dale") (field (name "Comment") "Res 0 ohm 0.1W"))
      (libsource (lib "Firstview") (part "Res 0 ohm 0.1W"))
    )
    (comp (ref "R270")
      (value "0 Ω")
      (footprint "RES_0402")
      (description "Res, 0 ohm, 1/16W, 0402")
      (fields (field (name "MANUFACTURER") "Vishay Dale") (field (name "Comment") "Res 0 ohm 0.1W"))
      (libsource (lib "Firstview") (part "Res 0 ohm 0.1W"))
    )
    (comp (ref "R271")
      (value "0 Ω")
      (footprint "RES_0402")
      (description "Res, 0 ohm, 1/16W, 0402")
      (fields (field (name "MANUFACTURER") "Vishay Dale") (field (name "Comment") "Res 0 ohm 0.1W"))
      (libsource (lib "Firstview") (part "Res 0 ohm 0.1W"))
    )
    (comp (ref "R272")
      (value "1M")
      (footprint "RES_0402")
      (description "Res, 1M, 0.063W, 1%, 0402")
      (fields (field (name "MANUFACTURER") "Yageo") (field (name "Comment") "Res 1M 0.063W"))
      (libsource (lib "Firstview") (part "Res 1M 0.063W"))
    )
    (comp (ref "R273")
      (value "1M")
      (footprint "RES_0402")
      (description "Res, 1M, 0.063W, 1%, 0402")
      (fields (field (name "MANUFACTURER") "Yageo") (field (name "Comment") "Res 1M 0.063W"))
      (libsource (lib "Firstview") (part "Res 1M 0.063W"))
    )
    (comp (ref "R274")
      (value "9.09K")
      (footprint "RES_0402")
      (description "Res, 9.09K, 0.063W, 1%, 0402")
      (fields
        (field (name "MANUFACTURER") "Stackpole Electronics Inc")
        (field (name "Comment") "Res 9.09K 0.063W")
      )
      (libsource (lib "Firstview") (part "Res 9.09K 0.063W"))
    )
    (comp (ref "R275")
      (value "1M")
      (footprint "RES_0402")
      (description "Res, 1M, 0.063W, 1%, 0402")
      (fields (field (name "MANUFACTURER") "Yageo") (field (name "Comment") "Res 1M 0.063W"))
      (libsource (lib "Firstview") (part "Res 1M 0.063W"))
    )
    (comp (ref "R276")
      (value "4.7K")
      (footprint "RES_0402")
      (description "Res, 4.70K, 0.063W, 1%, 0402")
      (fields (field (name "MANUFACTURER") "Vishay Dale") (field (name "Comment") "Res 4.7K 0.063W"))
      (libsource (lib "Firstview") (part "Res 4.7K 0.063W"))
    )
    (comp (ref "R277")
      (value "10K")
      (footprint "RES_0402")
      (description "Res, 10K, 1/16W, 1%, 0402")
      (fields (field (name "MANUFACTURER") "Yageo") (field (name "Comment") "Res 10K 0.063W"))
      (libsource (lib "Firstview") (part "Res 10K 0.063W"))
    )
    (comp (ref "R278")
      (value "1M")
      (footprint "RES_0402")
      (description "Res, 1M, 0.063W, 1%, 0402")
      (fields (field (name "MANUFACTURER") "Yageo") (field (name "Comment") "Res 1M 0.063W"))
      (libsource (lib "Firstview") (part "Res 1M 0.063W"))
    )
    (comp (ref "R279")
      (value "4.7K")
      (footprint "RES_0402")
      (description "Res, 4.70K, 0.063W, 1%, 0402")
      (fields (field (name "MANUFACTURER") "Vishay Dale") (field (name "Comment") "Res 4.7K 0.063W"))
      (libsource (lib "Firstview") (part "Res 4.7K 0.063W"))
    )
    (comp (ref "R280")
      (value "10K")
      (footprint "RES_0402")
      (description "Res, 10K, 1/16W, 1%, 0402")
      (fields (field (name "MANUFACTURER") "Yageo") (field (name "Comment") "Res 10K 0.063W"))
      (libsource (lib "Firstview") (part "Res 10K 0.063W"))
    )
    (comp (ref "R281")
      (value "10K")
      (footprint "RES_0402")
      (description "Res, 10K, 1/16W, 1%, 0402")
      (fields (field (name "MANUFACTURER") "Yageo") (field (name "Comment") "Res 10K 0.063W"))
      (libsource (lib "Firstview") (part "Res 10K 0.063W"))
    )
    (comp (ref "R282")
      (value "10K")
      (footprint "RES_0402")
      (description "Res, 10K, 1/16W, 1%, 0402")
      (fields (field (name "MANUFACTURER") "Yageo") (field (name "Comment") "Res 10K 0.063W"))
      (libsource (lib "Firstview") (part "Res 10K 0.063W"))
    )
    (comp (ref "R283")
      (value "10K")
      (footprint "RES_0402")
      (description "Res, 10K, 1/16W, 1%, 0402")
      (fields (field (name "MANUFACTURER") "Yageo") (field (name "Comment") "Res 10K 0.063W"))
      (libsource (lib "Firstview") (part "Res 10K 0.063W"))
    )
    (comp (ref "R284")
      (value "1.87K")
      (footprint "RES_0402")
      (description "Res, 1.87K, 0.063W, 1%, 0402")
      (fields (field (name "TOLERANCE") "1%") (field (name "MANUFACTURER") "Stackpole Electronics Inc"))
      (libsource (lib "Firstview") (part "Res 1.87K 0.063W"))
    )
    (comp (ref "R285")
      (value "4.99K")
      (footprint "RES_0402")
      (description "Res, 4.99K, 0.063W, 1%, 0402")
      (fields
        (field (name "MANUFACTURER") "Samsung Electro-Mechanics America, Inc")
        (field (name "Comment") "Res 4.99K 0.063W")
      )
      (libsource (lib "Firstview") (part "Res 4.99K 0.063W"))
    )
    (comp (ref "R286")
      (value "30.9K")
      (footprint "RES_0402")
      (description "Res, 30.9K, 0.063W, 1%, 0402")
      (fields
        (field (name "MANUFACTURER") "Stackpole Electronics Inc")
        (field (name "Comment") "Res 30.9K 0.063W")
      )
      (libsource (lib "Firstview") (part "Res 30.9K 0.063W"))
    )
    (comp (ref "R287")
      (value "30.9K")
      (footprint "RES_0402")
      (description "Res, 30.9K, 0.063W, 1%, 0402")
      (fields
        (field (name "MANUFACTURER") "Stackpole Electronics Inc")
        (field (name "Comment") "Res 30.9K 0.063W")
      )
      (libsource (lib "Firstview") (part "Res 30.9K 0.063W"))
    )
    (comp (ref "R288")
      (value "0 Ω")
      (footprint "RES_0402")
      (description "Res, 0 ohm, 1/16W, 0402")
      (fields (field (name "MANUFACTURER") "Vishay Dale") (field (name "Comment") "Res 0 ohm 0.1W"))
      (libsource (lib "Firstview") (part "Res 0 ohm 0.1W"))
    )
    (comp (ref "R289")
      (value "0 Ω")
      (footprint "RES_0402")
      (description "Res, 0 ohm, 1/16W, 0402")
      (fields (field (name "MANUFACTURER") "Vishay Dale") (field (name "Comment") "Res 0 ohm 0.1W"))
      (libsource (lib "Firstview") (part "Res 0 ohm 0.1W"))
    )
    (comp (ref "R304")
      (value "0 Ω")
      (footprint "RES_0402")
      (description "Res, 0 ohm, 1/16W, 0402")
      (fields
        (field (name "MANUFACTURER") "Vishay Dale")
        (field (name "DNP") "DNP")
        (field (name "Comment") "Res 0 ohm 0.1W DNP")
      )
      (libsource (lib "Firstview") (part "Res 0 ohm 0.1W DNP"))
    )
    (comp (ref "R323")
      (value "0 Ω")
      (footprint "RES_0402")
      (description "Res, 0 ohm, 1/16W, 0402")
      (fields (field (name "MANUFACTURER") "Vishay Dale") (field (name "Comment") "Res 0 ohm 0.1W"))
      (libsource (lib "Firstview") (part "Res 0 ohm 0.1W"))
    )
    (comp (ref "R324")
      (value "0 Ω")
      (footprint "RES_0402")
      (description "Res, 0 ohm, 1/16W, 0402")
      (fields (field (name "MANUFACTURER") "Vishay Dale") (field (name "Comment") "Res 0 ohm 0.1W"))
      (libsource (lib "Firstview") (part "Res 0 ohm 0.1W"))
    )
    (comp (ref "R325")
      (value "0 Ω")
      (footprint "RES_0402")
      (description "Res, 0 ohm, 1/16W, 0402")
      (fields (field (name "MANUFACTURER") "Vishay Dale") (field (name "Comment") "Res 0 ohm 0.1W"))
      (libsource (lib "Firstview") (part "Res 0 ohm 0.1W"))
    )
    (comp (ref "R326")
      (value "0 Ω")
      (footprint "RES_0402")
      (description "Res, 0 ohm, 1/16W, 0402")
      (fields (field (name "MANUFACTURER") "Vishay Dale") (field (name "Comment") "Res 0 ohm 0.1W"))
      (libsource (lib "Firstview") (part "Res 0 ohm 0.1W"))
    )
    (comp (ref "R335")
      (value "0 Ω")
      (footprint "RES_0402")
      (description "Res, 0 ohm, 1/16W, 0402")
      (fields (field (name "MANUFACTURER") "Vishay Dale") (field (name "Comment") "Res 0 ohm 0.1W"))
      (libsource (lib "Firstview") (part "Res 0 ohm 0.1W"))
    )
    (comp (ref "U33")
      (value "TPD2EUSB30ADRTR")
      (footprint "SOT-3_TPD2EUSB30ADRTR")
      (description "Diode, TVS, 3.6VWM, 8VC, SOT-3")
      (fields (field (name "MANUFACTURER") "Texas Instruments"))
      (libsource (lib "Firstview") (part "TPD2EUSB30ADRTR"))
    )
    (comp (ref "U34")
      (value "TUSB7340IRKMT")
      (footprint "WQFN-100_TUSB7340")
      (description "IC, 4-PORT USB 3.0 xHCI Host HUB, WQFN-100")
      (fields (field (name "MANUFACTURER") "Texas Instruments"))
      (libsource (lib "Firstview") (part "TUSB7340IRKMT"))
    )
    (comp (ref "U35")
      (value "TPD2EUSB30ADRTR")
      (footprint "SOT-3_TPD2EUSB30ADRTR")
      (description "Diode, TVS, 3.6VWM, 8VC, SOT-3")
      (fields (field (name "MANUFACTURER") "Texas Instruments"))
      (libsource (lib "Firstview") (part "TPD2EUSB30ADRTR"))
    )
    (comp (ref "U36")
      (value "TPD2EUSB30ADRTR")
      (footprint "SOT-3_TPD2EUSB30ADRTR")
      (description "Diode, TVS, 3.6VWM, 8VC, SOT-3")
      (fields (field (name "MANUFACTURER") "Texas Instruments"))
      (libsource (lib "Firstview") (part "TPD2EUSB30ADRTR"))
    )
    (comp (ref "U37")
      (value "TPD2EUSB30ADRTR")
      (footprint "SOT-3_TPD2EUSB30ADRTR")
      (description "Diode, TVS, 3.6VWM, 8VC, SOT-3")
      (fields (field (name "MANUFACTURER") "Texas Instruments"))
      (libsource (lib "Firstview") (part "TPD2EUSB30ADRTR"))
    )
    (comp (ref "U38")
      (value "TPS74401RGWT")
      (footprint "VQFN-20_TPS74401RGWT")
      (description "LDO, Adj., 3A, VQFN-20")
      (fields (field (name "MANUFACTURER") "Texas Instruments"))
      (libsource (lib "Firstview") (part "TPS74401RGWT"))
    )
    (comp (ref "U39")
      (value "TPS2560DRCT")
      (footprint "VSON-10_TPS2560DRCT")
      (description "IC, Power Dist Switch, Adj., VSON-10")
      (fields (field (name "MANUFACTURER") "Texas Instruments"))
      (libsource (lib "Firstview") (part "TPS2560DRC"))
    )
    (comp (ref "U40")
      (value "TPS2560DRCT")
      (footprint "VSON-10_TPS2560DRCT")
      (description "IC, Power Dist Switch, Adj., VSON-10")
      (fields (field (name "MANUFACTURER") "Texas Instruments"))
      (libsource (lib "Firstview") (part "TPS2560DRCT"))
    )
    (comp (ref "Y6")
      (value "48 MHz")
      (footprint "SMD(5x3.2)_ABM3B-48.000MHZ-B2-T")
      (description "Clock, Crystal, 48 MHz, 18pF, SMD")
      (fields (field (name "MANUFACTURER") "Abracon LLC") (field (name "Comment") "ABM3B-48.000MHZ-B2-T"))
      (libsource (lib "Firstview") (part "ABM3B-48.000MHZ-B2-T"))
    )
  )
  (nets
    (net (code "1") (name "/AUX_DET") (class "Default")
      (node (ref "R266") (pin "2") (pinfunction "2_2") (pintype "passive"))
      (node (ref "R268") (pin "1") (pinfunction "1_1") (pintype "passive"))
      (node (ref "R269") (pin "1") (pinfunction "1_1") (pintype "passive"))
      (node (ref "U34") (pin "A52") (pinfunction "AUX_DET_A52") (pintype "passive"))
    )
    (net (code "2") (name "/CAP_DS_TX1_N") (class "Default")
      (node (ref "C366") (pin "2") (pinfunction "2_2") (pintype "passive"))
      (node (ref "FB23") (pin "1") (pinfunction "1_1") (pintype "passive"))
    )
    (net (code "3") (name "/CAP_DS_TX1_P") (class "Default")
      (node (ref "C378") (pin "2") (pinfunction "2_2") (pintype "passive"))
      (node (ref "FB23") (pin "2") (pinfunction "2_2") (pintype "passive"))
    )
    (net (code "4") (name "/CAP_DS_TX2_N") (class "Default")
      (node (ref "C381") (pin "2") (pinfunction "2_2") (pintype "passive"))
      (node (ref "FB25") (pin "1") (pinfunction "1_1") (pintype "passive"))
    )
    (net (code "5") (name "/CAP_DS_TX2_P") (class "Default")
      (node (ref "C382") (pin "2") (pinfunction "2_2") (pintype "passive"))
      (node (ref "FB25") (pin "2") (pinfunction "2_2") (pintype "passive"))
    )
    (net (code "6") (name "/CAP_DS_TX3_N") (class "Default")
      (node (ref "C385") (pin "2") (pinfunction "2_2") (pintype "passive"))
      (node (ref "FB27") (pin "1") (pinfunction "1_1") (pintype "passive"))
    )
    (net (code "7") (name "/CAP_DS_TX3_P") (class "Default")
      (node (ref "C386") (pin "2") (pinfunction "2_2") (pintype "passive"))
      (node (ref "FB27") (pin "2") (pinfunction "2_2") (pintype "passive"))
    )
    (net (code "8") (name "/CAP_DS_TX4_N") (class "Default")
      (node (ref "C389") (pin "2") (pinfunction "2_2") (pintype "passive"))
      (node (ref "FB29") (pin "1") (pinfunction "1_1") (pintype "passive"))
    )
    (net (code "9") (name "/CAP_DS_TX4_P") (class "Default")
      (node (ref "C390") (pin "2") (pinfunction "2_2") (pintype "passive"))
      (node (ref "FB29") (pin "2") (pinfunction "2_2") (pintype "passive"))
    )
    (net (code "10") (name "/GRSTZ") (class "Default")
      (node (ref "C393") (pin "1") (pinfunction "1_1") (pintype "passive"))
      (node (ref "R277") (pin "2") (pinfunction "2_2") (pintype "passive"))
      (node (ref "U34") (pin "A15") (pinfunction "GRST#_A15") (pintype "passive"))
      (node (ref "U38") (pin "9") (pinfunction "PG_9") (pintype "passive"))
    )
    (net (code "11") (name "/IND_DS_TX1_N") (class "Default")
      (node (ref "FB23") (pin "4") (pinfunction "4_4") (pintype "passive"))
      (node (ref "J9") (pin "8") (pinfunction "SSTXN_8") (pintype "passive"))
    )
    (net (code "12") (name "/IND_DS_TX1_P") (class "Default")
      (node (ref "FB23") (pin "3") (pinfunction "3_3") (pintype "passive"))
      (node (ref "J9") (pin "9") (pinfunction "SSTXP_9") (pintype "passive"))
    )
    (net (code "13") (name "/IND_DS_TX2_N") (class "Default")
      (node (ref "FB25") (pin "4") (pinfunction "4_4") (pintype "passive"))
      (node (ref "J10") (pin "8") (pinfunction "SSTXN_8") (pintype "passive"))
    )
    (net (code "14") (name "/IND_DS_TX2_P") (class "Default")
      (node (ref "FB25") (pin "3") (pinfunction "3_3") (pintype "passive"))
      (node (ref "J10") (pin "9") (pinfunction "SSTXP_9") (pintype "passive"))
    )
    (net (code "15") (name "/IND_DS_TX3_N") (class "Default")
      (node (ref "FB27") (pin "4") (pinfunction "4_4") (pintype "passive"))
      (node (ref "J11") (pin "8") (pinfunction "SSTXN_8") (pintype "passive"))
    )
    (net (code "16") (name "/IND_DS_TX3_P") (class "Default")
      (node (ref "FB27") (pin "3") (pinfunction "3_3") (pintype "passive"))
      (node (ref "J11") (pin "9") (pinfunction "SSTXP_9") (pintype "passive"))
    )
    (net (code "17") (name "/IND_DS_TX4_N") (class "Default")
      (node (ref "FB29") (pin "4") (pinfunction "4_4") (pintype "passive"))
      (node (ref "J12") (pin "8") (pinfunction "SSTXN_8") (pintype "passive"))
    )
    (net (code "18") (name "/IND_DS_TX4_P") (class "Default")
      (node (ref "FB29") (pin "3") (pinfunction "3_3") (pintype "passive"))
      (node (ref "J12") (pin "9") (pinfunction "SSTXP_9") (pintype "passive"))
    )
    (net (code "19") (name "/IND_USB_D_DN1_N") (class "Default")
      (node (ref "FB22") (pin "4") (pinfunction "4_4") (pintype "passive"))
      (node (ref "J9") (pin "2") (pinfunction "DM_2") (pintype "passive"))
    )
    (net (code "20") (name "/IND_USB_D_DN1_P") (class "Default")
      (node (ref "FB22") (pin "3") (pinfunction "3_3") (pintype "passive"))
      (node (ref "J9") (pin "3") (pinfunction "DP_3") (pintype "passive"))
    )
    (net (code "21") (name "/IND_USB_D_DN2_N") (class "Default")
      (node (ref "FB24") (pin "4") (pinfunction "4_4") (pintype "passive"))
      (node (ref "J10") (pin "2") (pinfunction "DM_2") (pintype "passive"))
    )
    (net (code "22") (name "/IND_USB_D_DN2_P") (class "Default")
      (node (ref "FB24") (pin "3") (pinfunction "3_3") (pintype "passive"))
      (node (ref "J10") (pin "3") (pinfunction "DP_3") (pintype "passive"))
    )
    (net (code "23") (name "/IND_USB_D_DN3_N") (class "Default")
      (node (ref "FB26") (pin "4") (pinfunction "4_4") (pintype "passive"))
      (node (ref "J11") (pin "2") (pinfunction "DM_2") (pintype "passive"))
    )
    (net (code "24") (name "/IND_USB_D_DN3_P") (class "Default")
      (node (ref "FB26") (pin "3") (pinfunction "3_3") (pintype "passive"))
      (node (ref "J11") (pin "3") (pinfunction "DP_3") (pintype "passive"))
    )
    (net (code "25") (name "/IND_USB_D_DN4_N") (class "Default")
      (node (ref "FB28") (pin "4") (pinfunction "4_4") (pintype "passive"))
      (node (ref "J12") (pin "2") (pinfunction "DM_2") (pintype "passive"))
    )
    (net (code "26") (name "/IND_USB_D_DN4_P") (class "Default")
      (node (ref "FB28") (pin "3") (pinfunction "3_3") (pintype "passive"))
      (node (ref "J12") (pin "3") (pinfunction "DP_3") (pintype "passive"))
    )
    (net (code "27") (name "/OVERCURRENTZ1") (class "Default")
      (node (ref "R281") (pin "2") (pinfunction "2_2") (pintype "passive"))
      (node (ref "U34") (pin "A36") (pinfunction "OVERCUR1#_A36") (pintype "passive"))
      (node (ref "U39") (pin "6") (pinfunction "FAULT2Z_6") (pintype "passive"))
    )
    (net (code "28") (name "/OVERCURRENTZ2") (class "Default")
      (node (ref "R282") (pin "2") (pinfunction "2_2") (pintype "passive"))
      (node (ref "U34") (pin "A37") (pinfunction "OVERCUR2#_A37") (pintype "passive"))
      (node (ref "U40") (pin "10") (pinfunction "FAULT1Z_10") (pintype "passive"))
    )
    (net (code "29") (name "/OVERCURRENTZ3") (class "Default")
      (node (ref "R280") (pin "2") (pinfunction "2_2") (pintype "passive"))
      (node (ref "U34") (pin "B43") (pinfunction "OVERCUR3#_B43") (pintype "passive"))
      (node (ref "U39") (pin "10") (pinfunction "FAULT1Z_10") (pintype "passive"))
    )
    (net (code "30") (name "/OVERCURRENTZ4") (class "Default")
      (node (ref "R283") (pin "2") (pinfunction "2_2") (pintype "passive"))
      (node (ref "U34") (pin "B45") (pinfunction "OVERCUR4#_B45") (pintype "passive"))
      (node (ref "U40") (pin "6") (pinfunction "FAULT2Z_6") (pintype "passive"))
    )
    (net (code "31") (name "/PCIECLK_N") (class "Default")
      (node (ref "R323") (pin "2") (pinfunction "2_2") (pintype "passive"))
      (node (ref "U34") (pin "B41") (pinfunction "PCIE_REFCLKN_B41") (pintype "input"))
    )
    (net (code "32") (name "/PCIECLK_P") (class "Default")
      (node (ref "R324") (pin "2") (pinfunction "2_2") (pintype "passive"))
      (node (ref "U34") (pin "A45") (pinfunction "PCIE_REFCLKP_A45") (pintype "input"))
    )
    (net (code "33") (name "/PCIERX_N") (class "Default")
      (node (ref "C418") (pin "2") (pinfunction "2_2") (pintype "passive"))
      (node (ref "U34") (pin "A41") (pinfunction "PCIE_TXN_A41") (pintype "output"))
    )
    (net (code "34") (name "/PCIERX_P") (class "Default")
      (node (ref "C419") (pin "2") (pinfunction "2_2") (pintype "passive"))
      (node (ref "U34") (pin "B38") (pinfunction "PCIE_TXP_B38") (pintype "output"))
    )
    (net (code "35") (name "/PCIETX_N") (class "Default")
      (node (ref "R325") (pin "2") (pinfunction "2_2") (pintype "passive"))
      (node (ref "U34") (pin "A42") (pinfunction "PCIE_RXN_A42") (pintype "input"))
    )
    (net (code "36") (name "/PCIETX_P") (class "Default")
      (node (ref "R326") (pin "2") (pinfunction "2_2") (pintype "passive"))
      (node (ref "U34") (pin "B39") (pinfunction "PCIE_RXP_B39") (pintype "input"))
    )
    (net (code "37") (name "/PCIE_CLK_N") (class "Default")
      (node (ref "R323") (pin "1") (pinfunction "1_1") (pintype "passive"))
    )
    (net (code "38") (name "/PCIE_CLK_P") (class "Default")
      (node (ref "R324") (pin "1") (pinfunction "1_1") (pintype "passive"))
    )
    (net (code "39") (name "/PCIE_RX_N") (class "Default")
      (node (ref "C418") (pin "1") (pinfunction "1_1") (pintype "passive"))
    )
    (net (code "40") (name "/PCIE_RX_P") (class "Default")
      (node (ref "C419") (pin "1") (pinfunction "1_1") (pintype "passive"))
    )
    (net (code "41") (name "/PCIE_TX_N") (class "Default")
      (node (ref "R325") (pin "1") (pinfunction "1_1") (pintype "passive"))
    )
    (net (code "42") (name "/PCIE_TX_P") (class "Default")
      (node (ref "R326") (pin "1") (pinfunction "1_1") (pintype "passive"))
    )
    (net (code "43") (name "/PERST#") (class "Default")
      (node (ref "R288") (pin "2") (pinfunction "2_2") (pintype "passive"))
      (node (ref "U34") (pin "A40") (pinfunction "PERST#_A40") (pintype "passive"))
    )
    (net (code "44") (name "/PWRON1") (class "Default")
      (node (ref "U34") (pin "B33") (pinfunction "PWRON1#_B33") (pintype "passive"))
      (node (ref "U39") (pin "5") (pinfunction "EN2_5") (pintype "passive"))
    )
    (net (code "45") (name "/PWRON2") (class "Default")
      (node (ref "U34") (pin "B34") (pinfunction "PWRON2#_B34") (pintype "passive"))
      (node (ref "U40") (pin "4") (pinfunction "EN1_4") (pintype "passive"))
    )
    (net (code "46") (name "/PWRON3") (class "Default")
      (node (ref "U34") (pin "A46") (pinfunction "PWRON3#_A46") (pintype "passive"))
      (node (ref "U39") (pin "4") (pinfunction "EN1_4") (pintype "passive"))
    )
    (net (code "47") (name "/PWRON4") (class "Default")
      (node (ref "U34") (pin "A48") (pinfunction "PWRON4#_A48") (pintype "passive"))
      (node (ref "U40") (pin "5") (pinfunction "EN2_5") (pintype "passive"))
    )
    (net (code "48") (name "/USB_D_DN1_N") (class "Default")
      (node (ref "FB22") (pin "1") (pinfunction "1_1") (pintype "passive"))
      (node (ref "U34") (pin "B18") (pinfunction "USB_DM_DN1_B18") (pintype "passive"))
    )
    (net (code "49") (name "/USB_D_DN1_P") (class "Default")
      (node (ref "FB22") (pin "2") (pinfunction "2_2") (pintype "passive"))
      (node (ref "U34") (pin "A20") (pinfunction "USB_DP_DN1_A20") (pintype "passive"))
    )
    (net (code "50") (name "/USB_D_DN2_N") (class "Default")
      (node (ref "FB24") (pin "1") (pinfunction "1_1") (pintype "passive"))
      (node (ref "U34") (pin "A13") (pinfunction "USB_DM_DN2_A13") (pintype "passive"))
    )
    (net (code "51") (name "/USB_D_DN2_P") (class "Default")
      (node (ref "FB24") (pin "2") (pinfunction "2_2") (pintype "passive"))
      (node (ref "U34") (pin "B12") (pinfunction "USB_DP_DN2_B12") (pintype "passive"))
    )
    (net (code "52") (name "/USB_D_DN3_N") (class "Default")
      (node (ref "FB26") (pin "1") (pinfunction "1_1") (pintype "passive"))
      (node (ref "U34") (pin "A27") (pinfunction "USB_DM_DN3_A27") (pintype "passive"))
    )
    (net (code "53") (name "/USB_D_DN3_P") (class "Default")
      (node (ref "FB26") (pin "2") (pinfunction "2_2") (pintype "passive"))
      (node (ref "U34") (pin "B25") (pinfunction "USB_DP_DN3_B25") (pintype "passive"))
    )
    (net (code "54") (name "/USB_D_DN4_N") (class "Default")
      (node (ref "FB28") (pin "1") (pinfunction "1_1") (pintype "passive"))
      (node (ref "U34") (pin "A5") (pinfunction "USB_DM_DN4_A5") (pintype "passive"))
    )
    (net (code "55") (name "/USB_D_DN4_P") (class "Default")
      (node (ref "FB28") (pin "2") (pinfunction "2_2") (pintype "passive"))
      (node (ref "U34") (pin "B5") (pinfunction "USB_DP_DN4_B5") (pintype "passive"))
    )
    (net (code "56") (name "/USB_SSRX_DN1_N") (class "Default")
      (node (ref "J9") (pin "5") (pinfunction "SSRXN_5") (pintype "passive"))
      (node (ref "U33") (pin "2") (pinfunction "D-_2") (pintype "passive"))
      (node (ref "U34") (pin "B16") (pinfunction "USB_SSRXN_DN1_B16") (pintype "passive"))
    )
    (net (code "57") (name "/USB_SSRX_DN1_P") (class "Default")
      (node (ref "J9") (pin "6") (pinfunction "SSRXP_6") (pintype "passive"))
      (node (ref "U33") (pin "1") (pinfunction "D+_1") (pintype "passive"))
      (node (ref "U34") (pin "A18") (pinfunction "USB_SSRXP_DN1_A18") (pintype "passive"))
    )
    (net (code "58") (name "/USB_SSRX_DN2_N") (class "Default")
      (node (ref "J10") (pin "5") (pinfunction "SSRXN_5") (pintype "passive"))
      (node (ref "U34") (pin "A10") (pinfunction "USB_SSRXN_DN2_A10") (pintype "passive"))
      (node (ref "U35") (pin "2") (pinfunction "D-_2") (pintype "passive"))
    )
    (net (code "59") (name "/USB_SSRX_DN2_P") (class "Default")
      (node (ref "J10") (pin "6") (pinfunction "SSRXP_6") (pintype "passive"))
      (node (ref "U34") (pin "B9") (pinfunction "USB_SSRXP_DN2_B9") (pintype "passive"))
      (node (ref "U35") (pin "1") (pinfunction "D+_1") (pintype "passive"))
    )
    (net (code "60") (name "/USB_SSRX_DN3_N") (class "Default")
      (node (ref "J11") (pin "5") (pinfunction "SSRXN_5") (pintype "passive"))
      (node (ref "U34") (pin "A29") (pinfunction "USB_SSRXN_DN_A29") (pintype "passive"))
      (node (ref "U36") (pin "2") (pinfunction "D-_2") (pintype "passive"))
    )
    (net (code "61") (name "/USB_SSRX_DN3_P") (class "Default")
      (node (ref "J11") (pin "6") (pinfunction "SSRXP_6") (pintype "passive"))
      (node (ref "U34") (pin "B27") (pinfunction "USB_SSRXP_DN3_B27") (pintype "passive"))
      (node (ref "U36") (pin "1") (pinfunction "D+_1") (pintype "passive"))
    )
    (net (code "62") (name "/USB_SSRX_DN4_N") (class "Default")
      (node (ref "J12") (pin "5") (pinfunction "SSRXN_5") (pintype "passive"))
      (node (ref "U34") (pin "A7") (pinfunction "USB_SSRXN_DN4_A7") (pintype "passive"))
      (node (ref "U37") (pin "2") (pinfunction "D-_2") (pintype "passive"))
    )
    (net (code "63") (name "/USB_SSRX_DN4_P") (class "Default")
      (node (ref "J12") (pin "6") (pinfunction "SSRXP_6") (pintype "passive"))
      (node (ref "U34") (pin "B6") (pinfunction "USB_SSRXP_DN4_B6") (pintype "passive"))
      (node (ref "U37") (pin "1") (pinfunction "D+_1") (pintype "passive"))
    )
    (net (code "64") (name "/USB_SSTX_DN1_N") (class "Default")
      (node (ref "C366") (pin "1") (pinfunction "1_1") (pintype "passive"))
      (node (ref "U34") (pin "B15") (pinfunction "USB_SSTXN_DN1_B15") (pintype "passive"))
    )
    (net (code "65") (name "/USB_SSTX_DN1_P") (class "Default")
      (node (ref "C378") (pin "1") (pinfunction "1_1") (pintype "passive"))
      (node (ref "U34") (pin "A17") (pinfunction "USB_SSTXP_DN1_A17") (pintype "passive"))
    )
    (net (code "66") (name "/USB_SSTX_DN2_N") (class "Default")
      (node (ref "C381") (pin "1") (pinfunction "1_1") (pintype "passive"))
      (node (ref "U34") (pin "B10") (pinfunction "USB_SSTXN_DN2_B10") (pintype "passive"))
    )
    (net (code "67") (name "/USB_SSTX_DN2_P") (class "Default")
      (node (ref "C382") (pin "1") (pinfunction "1_1") (pintype "passive"))
      (node (ref "U34") (pin "A11") (pinfunction "USB_SSTXP_DN2_A11") (pintype "passive"))
    )
    (net (code "68") (name "/USB_SSTX_DN3_N") (class "Default")
      (node (ref "C385") (pin "1") (pinfunction "1_1") (pintype "passive"))
      (node (ref "U34") (pin "A30") (pinfunction "USB_SSTXN_DN3_A30") (pintype "passive"))
    )
    (net (code "69") (name "/USB_SSTX_DN3_P") (class "Default")
      (node (ref "C386") (pin "1") (pinfunction "1_1") (pintype "passive"))
      (node (ref "U34") (pin "B28") (pinfunction "USB_SSTXP_DN3_B28") (pintype "passive"))
    )
    (net (code "70") (name "/USB_SSTX_DN4_N") (class "Default")
      (node (ref "C389") (pin "1") (pinfunction "1_1") (pintype "passive"))
      (node (ref "U34") (pin "A8") (pinfunction "USB_SSTXN_DN4_A8") (pintype "passive"))
    )
    (net (code "71") (name "/USB_SSTX_DN4_P") (class "Default")
      (node (ref "C390") (pin "1") (pinfunction "1_1") (pintype "passive"))
      (node (ref "U34") (pin "B7") (pinfunction "USB_SSTXP_DN4_B7") (pintype "passive"))
    )
    (net (code "72") (name "/WAKE#") (class "Default")
      (node (ref "R289") (pin "2") (pinfunction "2_2") (pintype "passive"))
      (node (ref "U34") (pin "B35") (pinfunction "WAKE#_B35") (pintype "passive"))
    )
    (net (code "73") (name "/~{PERSTZ}") (class "Default")
      (node (ref "R288") (pin "1") (pinfunction "1_1") (pintype "passive"))
    )
    (net (code "74") (name "/~{WAKEZ}") (class "Default")
      (node (ref "R289") (pin "1") (pinfunction "1_1") (pintype "passive"))
    )
    (net (code "75") (name "1.1V") (class "Default")
      (node (ref "C354") (pin "1") (pinfunction "1_1") (pintype "passive"))
      (node (ref "C355") (pin "1") (pinfunction "1_1") (pintype "passive"))
      (node (ref "C356") (pin "1") (pinfunction "1_1") (pintype "passive"))
      (node (ref "C357") (pin "1") (pinfunction "1_1") (pintype "passive"))
      (node (ref "C358") (pin "1") (pinfunction "1_1") (pintype "passive"))
      (node (ref "C359") (pin "1") (pinfunction "1_1") (pintype "passive"))
      (node (ref "C360") (pin "1") (pinfunction "1_1") (pintype "passive"))
      (node (ref "C361") (pin "1") (pinfunction "1_1") (pintype "passive"))
      (node (ref "C362") (pin "1") (pinfunction "1_1") (pintype "passive"))
      (node (ref "C363") (pin "1") (pinfunction "1_1") (pintype "passive"))
      (node (ref "C364") (pin "1") (pinfunction "1_1") (pintype "passive"))
      (node (ref "C365") (pin "1") (pinfunction "1_1") (pintype "passive"))
      (node (ref "C367") (pin "1") (pinfunction "1_1") (pintype "passive"))
      (node (ref "C368") (pin "1") (pinfunction "1_1") (pintype "passive"))
      (node (ref "C369") (pin "1") (pinfunction "1_1") (pintype "passive"))
      (node (ref "C370") (pin "1") (pinfunction "1_1") (pintype "passive"))
      (node (ref "C371") (pin "1") (pinfunction "1_1") (pintype "passive"))
      (node (ref "C372") (pin "1") (pinfunction "1_1") (pintype "passive"))
      (node (ref "C373") (pin "1") (pinfunction "1_1") (pintype "passive"))
      (node (ref "C374") (pin "1") (pinfunction "1_1") (pintype "passive"))
      (node (ref "C375") (pin "1") (pinfunction "1_1") (pintype "passive"))
      (node (ref "C376") (pin "1") (pinfunction "1_1") (pintype "passive"))
      (node (ref "C377") (pin "1") (pinfunction "1_1") (pintype "passive"))
      (node (ref "C397") (pin "1") (pinfunction "1_1") (pintype "passive"))
      (node (ref "R284") (pin "1") (pinfunction "1_1") (pintype "passive"))
      (node (ref "R304") (pin "1") (pinfunction "1_1") (pintype "passive"))
      (node (ref "U34") (pin "A1") (pinfunction "VDD11_A1") (pintype "passive"))
      (node (ref "U34") (pin "A12") (pinfunction "VDD11_A12") (pintype "passive"))
      (node (ref "U34") (pin "A16") (pinfunction "VDD11_A16") (pintype "passive"))
      (node (ref "U34") (pin "A28") (pinfunction "VDD11_A28") (pintype "passive"))
      (node (ref "U34") (pin "A31") (pinfunction "VDD11_A31") (pintype "passive"))
      (node (ref "U34") (pin "A33") (pinfunction "VDD11_A33") (pintype "passive"))
      (node (ref "U34") (pin "A38") (pinfunction "VDD11_A38") (pintype "passive"))
      (node (ref "U34") (pin "A4") (pinfunction "VDD11_A4") (pintype "passive"))
      (node (ref "U34") (pin "A50") (pinfunction "VDD11_A50") (pintype "passive"))
      (node (ref "U34") (pin "A6") (pinfunction "VDD11_A6") (pintype "passive"))
      (node (ref "U34") (pin "A9") (pinfunction "VDD11_A9") (pintype "passive"))
      (node (ref "U34") (pin "B1") (pinfunction "VDD11_B1") (pintype "passive"))
      (node (ref "U34") (pin "B17") (pinfunction "VDD11_B17") (pintype "passive"))
      (node (ref "U34") (pin "B19") (pinfunction "VDD11_B19") (pintype "passive"))
      (node (ref "U34") (pin "B24") (pinfunction "VDD11_B24") (pintype "passive"))
      (node (ref "U34") (pin "B37") (pinfunction "VDD11_B37") (pintype "passive"))
      (node (ref "U34") (pin "B40") (pinfunction "VDD11_B40") (pintype "passive"))
      (node (ref "U34") (pin "B42") (pinfunction "VDD11_B42") (pintype "passive"))
      (node (ref "U34") (pin "B44") (pinfunction "VDD11_B44") (pintype "passive"))
      (node (ref "U38") (pin "1") (pinfunction "OUT_1") (pintype "passive"))
      (node (ref "U38") (pin "18") (pinfunction "OUT_18") (pintype "passive"))
      (node (ref "U38") (pin "19") (pinfunction "OUT_19") (pintype "passive"))
      (node (ref "U38") (pin "20") (pinfunction "OUT_20") (pintype "passive"))
    )
    (net (code "76") (name "3.3V_USBAN") (class "Default")
      (node (ref "C341") (pin "1") (pinfunction "1_1") (pintype "passive"))
      (node (ref "C342") (pin "1") (pinfunction "1_1") (pintype "passive"))
      (node (ref "C343") (pin "1") (pinfunction "1_1") (pintype "passive"))
      (node (ref "C349") (pin "1") (pinfunction "1_1") (pintype "passive"))
      (node (ref "C350") (pin "1") (pinfunction "1_1") (pintype "passive"))
      (node (ref "C351") (pin "1") (pinfunction "1_1") (pintype "passive"))
      (node (ref "C352") (pin "1") (pinfunction "1_1") (pintype "passive"))
      (node (ref "C353") (pin "1") (pinfunction "1_1") (pintype "passive"))
      (node (ref "FB21") (pin "2") (pinfunction "2_2") (pintype "passive"))
      (node (ref "U34") (pin "A19") (pinfunction "VDDA_3P3_A19") (pintype "passive"))
      (node (ref "U34") (pin "A21") (pinfunction "VDDA_3P3_A21") (pintype "passive"))
      (node (ref "U34") (pin "A25") (pinfunction "VDDA_3P3_A25") (pintype "passive"))
      (node (ref "U34") (pin "A44") (pinfunction "VDDA_3P3_A44") (pintype "passive"))
      (node (ref "U34") (pin "B11") (pinfunction "VDDA_3P3_B11") (pintype "passive"))
      (node (ref "U34") (pin "B22") (pinfunction "VDDA_3P3_B22") (pintype "passive"))
      (node (ref "U34") (pin "B26") (pinfunction "VDDA_3P3_B26") (pintype "passive"))
      (node (ref "U34") (pin "B4") (pinfunction "VDDA_3P3_B4") (pintype "passive"))
    )
    (net (code "77") (name "3V3SW") (class "Default")
      (node (ref "C344") (pin "1") (pinfunction "1_1") (pintype "passive"))
      (node (ref "C345") (pin "1") (pinfunction "1_1") (pintype "passive"))
      (node (ref "C346") (pin "1") (pinfunction "1_1") (pintype "passive"))
      (node (ref "C347") (pin "1") (pinfunction "1_1") (pintype "passive"))
      (node (ref "C348") (pin "1") (pinfunction "1_1") (pintype "passive"))
      (node (ref "C394") (pin "1") (pinfunction "1_1") (pintype "passive"))
      (node (ref "FB21") (pin "1") (pinfunction "1_1") (pintype "passive"))
      (node (ref "R266") (pin "1") (pinfunction "1_1") (pintype "passive"))
      (node (ref "R277") (pin "1") (pinfunction "1_1") (pintype "passive"))
      (node (ref "R279") (pin "1") (pinfunction "1_1") (pintype "passive"))
      (node (ref "R280") (pin "1") (pinfunction "1_1") (pintype "passive"))
      (node (ref "R281") (pin "1") (pinfunction "1_1") (pintype "passive"))
      (node (ref "R282") (pin "1") (pinfunction "1_1") (pintype "passive"))
      (node (ref "R283") (pin "1") (pinfunction "1_1") (pintype "passive"))
      (node (ref "U34") (pin "A3") (pinfunction "VDD33_A3") (pintype "passive"))
      (node (ref "U34") (pin "A34") (pinfunction "VDD33_A34") (pintype "passive"))
      (node (ref "U34") (pin "A39") (pinfunction "VDD33_A39") (pintype "passive"))
      (node (ref "U34") (pin "A47") (pinfunction "VDD33_A47") (pintype "passive"))
      (node (ref "U34") (pin "A51") (pinfunction "VDD33_A51") (pintype "passive"))
      (node (ref "U38") (pin "10") (pinfunction "BIAS_10") (pintype "passive"))
      (node (ref "U38") (pin "5") (pinfunction "IN_5") (pintype "passive"))
      (node (ref "U38") (pin "6") (pinfunction "IN_6") (pintype "passive"))
      (node (ref "U38") (pin "7") (pinfunction "IN_7") (pintype "passive"))
      (node (ref "U38") (pin "8") (pinfunction "IN_8") (pintype "passive"))
    )
    (net (code "78") (name "5VSW") (class "Default")
      (node (ref "C395") (pin "1") (pinfunction "1_1") (pintype "passive"))
      (node (ref "C396") (pin "2") (pinfunction "2_2") (pintype "passive"))
      (node (ref "U39") (pin "2") (pinfunction "IN_2") (pintype "passive"))
      (node (ref "U39") (pin "3") (pinfunction "IN_3") (pintype "passive"))
      (node (ref "U40") (pin "2") (pinfunction "IN_2") (pintype "passive"))
      (node (ref "U40") (pin "3") (pinfunction "IN_3") (pintype "passive"))
    )
    (net (code "79") (name "DS1_VUSB") (class "Default")
      (node (ref "C404") (pin "1") (pinfunction "1_1") (pintype "passive"))
      (node (ref "C405") (pin "1") (pinfunction "1_1") (pintype "passive"))
      (node (ref "J9") (pin "1") (pinfunction "VBUS_1") (pintype "passive"))
      (node (ref "U39") (pin "8") (pinfunction "OUT2_8") (pintype "passive"))
    )
    (net (code "80") (name "DS2_VUSB") (class "Default")
      (node (ref "C402") (pin "1") (pinfunction "1_1") (pintype "passive"))
      (node (ref "C403") (pin "1") (pinfunction "1_1") (pintype "passive"))
      (node (ref "J10") (pin "1") (pinfunction "VBUS_1") (pintype "passive"))
      (node (ref "U40") (pin "9") (pinfunction "OUT1_9") (pintype "passive"))
    )
    (net (code "81") (name "DS3_VUSB") (class "Default")
      (node (ref "C400") (pin "1") (pinfunction "1_1") (pintype "passive"))
      (node (ref "C401") (pin "1") (pinfunction "1_1") (pintype "passive"))
      (node (ref "J11") (pin "1") (pinfunction "VBUS_1") (pintype "passive"))
      (node (ref "U39") (pin "9") (pinfunction "OUT1_9") (pintype "passive"))
    )
    (net (code "82") (name "DS4_VUSB") (class "Default")
      (node (ref "C406") (pin "1") (pinfunction "1_1") (pintype "passive"))
      (node (ref "C407") (pin "1") (pinfunction "1_1") (pintype "passive"))
      (node (ref "J12") (pin "1") (pinfunction "VBUS_1") (pintype "passive"))
      (node (ref "U40") (pin "8") (pinfunction "OUT2_8") (pintype "passive"))
    )
    (net (code "83") (name "GND") (class "Default")
      (node (ref "C341") (pin "2") (pinfunction "2_2") (pintype "passive"))
      (node (ref "C342") (pin "2") (pinfunction "2_2") (pintype "passive"))
      (node (ref "C343") (pin "2") (pinfunction "2_2") (pintype "passive"))
      (node (ref "C344") (pin "2") (pinfunction "2_2") (pintype "passive"))
      (node (ref "C345") (pin "2") (pinfunction "2_2") (pintype "passive"))
      (node (ref "C346") (pin "2") (pinfunction "2_2") (pintype "passive"))
      (node (ref "C347") (pin "2") (pinfunction "2_2") (pintype "passive"))
      (node (ref "C348") (pin "2") (pinfunction "2_2") (pintype "passive"))
      (node (ref "C349") (pin "2") (pinfunction "2_2") (pintype "passive"))
      (node (ref "C350") (pin "2") (pinfunction "2_2") (pintype "passive"))
      (node (ref "C351") (pin "2") (pinfunction "2_2") (pintype "passive"))
      (node (ref "C352") (pin "2") (pinfunction "2_2") (pintype "passive"))
      (node (ref "C353") (pin "2") (pinfunction "2_2") (pintype "passive"))
      (node (ref "C354") (pin "2") (pinfunction "2_2") (pintype "passive"))
      (node (ref "C355") (pin "2") (pinfunction "2_2") (pintype "passive"))
      (node (ref "C356") (pin "2") (pinfunction "2_2") (pintype "passive"))
      (node (ref "C357") (pin "2") (pinfunction "2_2") (pintype "passive"))
      (node (ref "C358") (pin "2") (pinfunction "2_2") (pintype "passive"))
      (node (ref "C359") (pin "2") (pinfunction "2_2") (pintype "passive"))
      (node (ref "C360") (pin "2") (pinfunction "2_2") (pintype "passive"))
      (node (ref "C361") (pin "2") (pinfunction "2_2") (pintype "passive"))
      (node (ref "C362") (pin "2") (pinfunction "2_2") (pintype "passive"))
      (node (ref "C363") (pin "2") (pinfunction "2_2") (pintype "passive"))
      (node (ref "C364") (pin "2") (pinfunction "2_2") (pintype "passive"))
      (node (ref "C365") (pin "2") (pinfunction "2_2") (pintype "passive"))
      (node (ref "C367") (pin "2") (pinfunction "2_2") (pintype "passive"))
      (node (ref "C368") (pin "2") (pinfunction "2_2") (pintype "passive"))
      (node (ref "C369") (pin "2") (pinfunction "2_2") (pintype "passive"))
      (node (ref "C370") (pin "2") (pinfunction "2_2") (pintype "passive"))
      (node (ref "C371") (pin "2") (pinfunction "2_2") (pintype "passive"))
      (node (ref "C372") (pin "2") (pinfunction "2_2") (pintype "passive"))
      (node (ref "C373") (pin "2") (pinfunction "2_2") (pintype "passive"))
      (node (ref "C374") (pin "2") (pinfunction "2_2") (pintype "passive"))
      (node (ref "C375") (pin "2") (pinfunction "2_2") (pintype "passive"))
      (node (ref "C376") (pin "2") (pinfunction "2_2") (pintype "passive"))
      (node (ref "C377") (pin "2") (pinfunction "2_2") (pintype "passive"))
      (node (ref "C379") (pin "2") (pinfunction "2_2") (pintype "passive"))
      (node (ref "C380") (pin "2") (pinfunction "2_2") (pintype "passive"))
      (node (ref "C383") (pin "2") (pinfunction "2_2") (pintype "passive"))
      (node (ref "C384") (pin "2") (pinfunction "2_2") (pintype "passive"))
      (node (ref "C387") (pin "2") (pinfunction "2_2") (pintype "passive"))
      (node (ref "C388") (pin "2") (pinfunction "2_2") (pintype "passive"))
      (node (ref "C391") (pin "2") (pinfunction "2_2") (pintype "passive"))
      (node (ref "C392") (pin "2") (pinfunction "2_2") (pintype "passive"))
      (node (ref "C393") (pin "2") (pinfunction "2_2") (pintype "passive"))
      (node (ref "C394") (pin "2") (pinfunction "2_2") (pintype "passive"))
      (node (ref "C395") (pin "2") (pinfunction "2_2") (pintype "passive"))
      (node (ref "C396") (pin "1") (pinfunction "1_1") (pintype "passive"))
      (node (ref "C397") (pin "2") (pinfunction "2_2") (pintype "passive"))
      (node (ref "C398") (pin "2") (pinfunction "2_2") (pintype "passive"))
      (node (ref "C399") (pin "2") (pinfunction "2_2") (pintype "passive"))
      (node (ref "C400") (pin "2") (pinfunction "2_2") (pintype "passive"))
      (node (ref "C401") (pin "2") (pinfunction "2_2") (pintype "passive"))
      (node (ref "C402") (pin "2") (pinfunction "2_2") (pintype "passive"))
      (node (ref "C403") (pin "2") (pinfunction "2_2") (pintype "passive"))
      (node (ref "C404") (pin "2") (pinfunction "2_2") (pintype "passive"))
      (node (ref "C405") (pin "2") (pinfunction "2_2") (pintype "passive"))
      (node (ref "C406") (pin "2") (pinfunction "2_2") (pintype "passive"))
      (node (ref "C407") (pin "2") (pinfunction "2_2") (pintype "passive"))
      (node (ref "FB22") (pin "5") (pinfunction "GND_5") (pintype "passive"))
      (node (ref "FB22") (pin "6") (pinfunction "GND_6") (pintype "passive"))
      (node (ref "FB23") (pin "5") (pinfunction "GND_5") (pintype "passive"))
      (node (ref "FB23") (pin "6") (pinfunction "GND_6") (pintype "passive"))
      (node (ref "FB24") (pin "5") (pinfunction "GND_5") (pintype "passive"))
      (node (ref "FB24") (pin "6") (pinfunction "GND_6") (pintype "passive"))
      (node (ref "FB25") (pin "5") (pinfunction "GND_5") (pintype "passive"))
      (node (ref "FB25") (pin "6") (pinfunction "GND_6") (pintype "passive"))
      (node (ref "FB26") (pin "5") (pinfunction "GND_5") (pintype "passive"))
      (node (ref "FB26") (pin "6") (pinfunction "GND_6") (pintype "passive"))
      (node (ref "FB27") (pin "5") (pinfunction "GND_5") (pintype "passive"))
      (node (ref "FB27") (pin "6") (pinfunction "GND_6") (pintype "passive"))
      (node (ref "FB28") (pin "5") (pinfunction "GND_5") (pintype "passive"))
      (node (ref "FB28") (pin "6") (pinfunction "GND_6") (pintype "passive"))
      (node (ref "FB29") (pin "5") (pinfunction "GND_5") (pintype "passive"))
      (node (ref "FB29") (pin "6") (pinfunction "GND_6") (pintype "passive"))
      (node (ref "J10") (pin "4") (pinfunction "GND_4") (pintype "passive"))
      (node (ref "J10") (pin "7") (pinfunction "GND_7") (pintype "passive"))
      (node (ref "J11") (pin "4") (pinfunction "GND_4") (pintype "passive"))
      (node (ref "J11") (pin "7") (pinfunction "GND_7") (pintype "passive"))
      (node (ref "J12") (pin "4") (pinfunction "GND_4") (pintype "passive"))
      (node (ref "J12") (pin "7") (pinfunction "GND_7") (pintype "passive"))
      (node (ref "J9") (pin "4") (pinfunction "GND_4") (pintype "passive"))
      (node (ref "J9") (pin "7") (pinfunction "GND_7") (pintype "passive"))
      (node (ref "R267") (pin "2") (pinfunction "2_2") (pintype "passive"))
      (node (ref "R268") (pin "2") (pinfunction "2_2") (pintype "passive"))
      (node (ref "R269") (pin "2") (pinfunction "2_2") (pintype "passive"))
      (node (ref "R270") (pin "2") (pinfunction "2_2") (pintype "passive"))
      (node (ref "R271") (pin "2") (pinfunction "2_2") (pintype "passive"))
      (node (ref "R272") (pin "2") (pinfunction "2_2") (pintype "passive"))
      (node (ref "R273") (pin "2") (pinfunction "2_2") (pintype "passive"))
      (node (ref "R276") (pin "2") (pinfunction "2_2") (pintype "passive"))
      (node (ref "R278") (pin "2") (pinfunction "2_2") (pintype "passive"))
      (node (ref "R285") (pin "2") (pinfunction "2_2") (pintype "passive"))
      (node (ref "R286") (pin "2") (pinfunction "2_2") (pintype "passive"))
      (node (ref "R287") (pin "2") (pinfunction "2_2") (pintype "passive"))
      (node (ref "R335") (pin "2") (pinfunction "2_2") (pintype "passive"))
      (node (ref "U33") (pin "3") (pinfunction "GND_3") (pintype "passive"))
      (node (ref "U34") (pin "B20") (pinfunction "VSS_B20") (pintype "passive"))
      (node (ref "U34") (pin "B32") (pinfunction "JTAG_RST#_B32") (pintype "passive"))
      (node (ref "U34") (pin "PAD") (pinfunction "VSS_PAD") (pintype "passive"))
      (node (ref "U35") (pin "3") (pinfunction "GND_3") (pintype "passive"))
      (node (ref "U36") (pin "3") (pinfunction "GND_3") (pintype "passive"))
      (node (ref "U37") (pin "3") (pinfunction "GND_3") (pintype "passive"))
      (node (ref "U38") (pin "12") (pinfunction "GND_12") (pintype "passive"))
      (node (ref "U38") (pin "21") (pinfunction "PAD_21") (pintype "passive"))
      (node (ref "U39") (pin "1") (pinfunction "GND_1") (pintype "passive"))
      (node (ref "U39") (pin "11") (pinfunction "PAD_11") (pintype "passive"))
      (node (ref "U40") (pin "1") (pinfunction "GND_1") (pintype "passive"))
      (node (ref "U40") (pin "11") (pinfunction "PAD_11") (pintype "passive"))
    )
    (net (code "84") (name "Net-(J9-SHIELD0)") (class "Default")
      (node (ref "C379") (pin "1") (pinfunction "1_1") (pintype "passive"))
      (node (ref "C380") (pin "1") (pinfunction "1_1") (pintype "passive"))
      (node (ref "J9") (pin "10") (pinfunction "SHIELD0_10") (pintype "passive"))
      (node (ref "J9") (pin "11") (pinfunction "SHIELD1_11") (pintype "passive"))
      (node (ref "R267") (pin "1") (pinfunction "1_1") (pintype "passive"))
    )
    (net (code "85") (name "Net-(J10-SHIELD0)") (class "Default")
      (node (ref "C383") (pin "1") (pinfunction "1_1") (pintype "passive"))
      (node (ref "C384") (pin "1") (pinfunction "1_1") (pintype "passive"))
      (node (ref "J10") (pin "10") (pinfunction "SHIELD0_10") (pintype "passive"))
      (node (ref "J10") (pin "11") (pinfunction "SHIELD1_11") (pintype "passive"))
      (node (ref "R272") (pin "1") (pinfunction "1_1") (pintype "passive"))
    )
    (net (code "86") (name "Net-(J11-SHIELD0)") (class "Default")
      (node (ref "C387") (pin "1") (pinfunction "1_1") (pintype "passive"))
      (node (ref "C388") (pin "1") (pinfunction "1_1") (pintype "passive"))
      (node (ref "J11") (pin "10") (pinfunction "SHIELD0_10") (pintype "passive"))
      (node (ref "J11") (pin "11") (pinfunction "SHIELD1_11") (pintype "passive"))
      (node (ref "R273") (pin "1") (pinfunction "1_1") (pintype "passive"))
    )
    (net (code "87") (name "Net-(J12-SHIELD0)") (class "Default")
      (node (ref "C391") (pin "1") (pinfunction "1_1") (pintype "passive"))
      (node (ref "C392") (pin "1") (pinfunction "1_1") (pintype "passive"))
      (node (ref "J12") (pin "10") (pinfunction "SHIELD0_10") (pintype "passive"))
      (node (ref "J12") (pin "11") (pinfunction "SHIELD1_11") (pintype "passive"))
      (node (ref "R278") (pin "1") (pinfunction "1_1") (pintype "passive"))
    )
    (net (code "88") (name "Net-(R304-Pad2)") (class "Default")
      (node (ref "R304") (pin "2") (pinfunction "2_2") (pintype "passive"))
      (node (ref "U34") (pin "B8") (pinfunction "NC_B8") (pintype "passive"))
    )
    (net (code "89") (name "Net-(R335-Pad1)") (class "Default")
      (node (ref "R335") (pin "1") (pinfunction "1_1") (pintype "passive"))
      (node (ref "Y6") (pin "2") (pinfunction "2_2") (pintype "passive"))
      (node (ref "Y6") (pin "4") (pinfunction "4_4") (pintype "passive"))
    )
    (net (code "90") (name "Net-(U34-FREQSEL)") (class "Default")
      (node (ref "R276") (pin "1") (pinfunction "1_1") (pintype "passive"))
      (node (ref "U34") (pin "B14") (pinfunction "FREQSEL_B14") (pintype "passive"))
    )
    (net (code "91") (name "Net-(U34-R1EXT)") (class "Default")
      (node (ref "R274") (pin "2") (pinfunction "2_2") (pintype "passive"))
      (node (ref "U34") (pin "A24") (pinfunction "R1EXT_A24") (pintype "passive"))
    )
    (net (code "92") (name "Net-(U34-R1EXTRTN)") (class "Default")
      (node (ref "R274") (pin "1") (pinfunction "1_1") (pintype "passive"))
      (node (ref "U34") (pin "B23") (pinfunction "R1EXTRTN_B23") (pintype "passive"))
    )
    (net (code "93") (name "Net-(U34-SCL)") (class "Default")
      (node (ref "R270") (pin "1") (pinfunction "1_1") (pintype "passive"))
      (node (ref "U34") (pin "B2") (pinfunction "SCL_B2") (pintype "passive"))
    )
    (net (code "94") (name "Net-(U34-SDA)") (class "Default")
      (node (ref "R271") (pin "1") (pinfunction "1_1") (pintype "passive"))
      (node (ref "U34") (pin "A2") (pinfunction "SDA_A2") (pintype "passive"))
    )
    (net (code "95") (name "Net-(U34-VSS_OSC)") (class "Default")
      (node (ref "C408") (pin "1") (pinfunction "1_1") (pintype "passive"))
      (node (ref "C409") (pin "2") (pinfunction "2_2") (pintype "passive"))
      (node (ref "U34") (pin "B21") (pinfunction "VSS_OSC_B21") (pintype "passive"))
    )
    (net (code "96") (name "Net-(U34-XI)") (class "Default")
      (node (ref "C409") (pin "1") (pinfunction "1_1") (pintype "passive"))
      (node (ref "R275") (pin "2") (pinfunction "2_2") (pintype "passive"))
      (node (ref "U34") (pin "A23") (pinfunction "XI_A23") (pintype "passive"))
      (node (ref "Y6") (pin "3") (pinfunction "3_3") (pintype "passive"))
    )
    (net (code "97") (name "Net-(U34-XO)") (class "Default")
      (node (ref "C408") (pin "2") (pinfunction "2_2") (pintype "passive"))
      (node (ref "R275") (pin "1") (pinfunction "1_1") (pintype "passive"))
      (node (ref "U34") (pin "A22") (pinfunction "XO_A22") (pintype "passive"))
      (node (ref "Y6") (pin "1") (pinfunction "1_1") (pintype "passive"))
    )
    (net (code "98") (name "Net-(U38-EN)") (class "Default")
      (node (ref "C398") (pin "1") (pinfunction "1_1") (pintype "passive"))
      (node (ref "R279") (pin "2") (pinfunction "2_2") (pintype "passive"))
      (node (ref "U38") (pin "11") (pinfunction "EN_11") (pintype "passive"))
    )
    (net (code "99") (name "Net-(U38-FB{slash}SNS)") (class "Default")
      (node (ref "R284") (pin "2") (pinfunction "2_2") (pintype "passive"))
      (node (ref "R285") (pin "1") (pinfunction "1_1") (pintype "passive"))
      (node (ref "U38") (pin "16") (pinfunction "FB/SNS_16") (pintype "passive"))
    )
    (net (code "100") (name "Net-(U38-SS)") (class "Default")
      (node (ref "C399") (pin "1") (pinfunction "1_1") (pintype "passive"))
      (node (ref "U38") (pin "15") (pinfunction "SS_15") (pintype "passive"))
    )
    (net (code "101") (name "Net-(U39-ILIM)") (class "Default")
      (node (ref "R286") (pin "1") (pinfunction "1_1") (pintype "passive"))
      (node (ref "U39") (pin "7") (pinfunction "ILIM_7") (pintype "passive"))
    )
    (net (code "102") (name "Net-(U40-ILIM)") (class "Default")
      (node (ref "R287") (pin "1") (pinfunction "1_1") (pintype "passive"))
      (node (ref "U40") (pin "7") (pinfunction "ILIM_7") (pintype "passive"))
    )
    (net (code "103") (name "unconnected-(U34-CLKREQ#-PadB36)") (class "Default")
      (node (ref "U34") (pin "B36") (pinfunction "CLKREQ#_B36") (pintype "passive+no_connect"))
    )
    (net (code "104") (name "unconnected-(U34-GPIO0-PadA49)") (class "Default")
      (node (ref "U34") (pin "A49") (pinfunction "GPIO0_A49") (pintype "passive+no_connect"))
    )
    (net (code "105") (name "unconnected-(U34-GPIO1-PadB46)") (class "Default")
      (node (ref "U34") (pin "B46") (pinfunction "GPIO1_B46") (pintype "passive+no_connect"))
    )
    (net (code "106") (name "unconnected-(U34-GPIO2-PadB47)") (class "Default")
      (node (ref "U34") (pin "B47") (pinfunction "GPIO2_B47") (pintype "passive+no_connect"))
    )
    (net (code "107") (name "unconnected-(U34-GPIO3-PadB48)") (class "Default")
      (node (ref "U34") (pin "B48") (pinfunction "GPIO3_B48") (pintype "passive+no_connect"))
    )
    (net (code "108") (name "unconnected-(U34-JTAG_TCK-PadA32)") (class "Default")
      (node (ref "U34") (pin "A32") (pinfunction "JTAG_TCK_A32") (pintype "passive+no_connect"))
    )
    (net (code "109") (name "unconnected-(U34-JTAG_TDI-PadA35)") (class "Default")
      (node (ref "U34") (pin "A35") (pinfunction "JTAG_TDI_A35") (pintype "passive+no_connect"))
    )
    (net (code "110") (name "unconnected-(U34-JTAG_TDO-PadB31)") (class "Default")
      (node (ref "U34") (pin "B31") (pinfunction "JTAG_TDO_B31") (pintype "passive+no_connect"))
    )
    (net (code "111") (name "unconnected-(U34-JTAG_TMS-PadB30)") (class "Default")
      (node (ref "U34") (pin "B30") (pinfunction "JTAG_TMS_B30") (pintype "passive+no_connect"))
    )
    (net (code "112") (name "unconnected-(U34-NC-PadA14)") (class "Default")
      (node (ref "U34") (pin "A14") (pinfunction "NC_A14") (pintype "passive+no_connect"))
    )
    (net (code "113") (name "unconnected-(U34-NC-PadA26)") (class "Default")
      (node (ref "U34") (pin "A26") (pinfunction "NC_A26") (pintype "passive+no_connect"))
    )
    (net (code "114") (name "unconnected-(U34-NC-PadA43)") (class "Default")
      (node (ref "U34") (pin "A43") (pinfunction "NC_A43") (pintype "passive+no_connect"))
    )
    (net (code "115") (name "unconnected-(U34-NC-PadB13)") (class "Default")
      (node (ref "U34") (pin "B13") (pinfunction "NC_B13") (pintype "passive+no_connect"))
    )
    (net (code "116") (name "unconnected-(U34-NC-PadB29)") (class "Default")
      (node (ref "U34") (pin "B29") (pinfunction "NC_B29") (pintype "passive+no_connect"))
    )
    (net (code "117") (name "unconnected-(U34-SMI-PadB3)") (class "Default")
      (node (ref "U34") (pin "B3") (pinfunction "SMI_B3") (pintype "passive+no_connect"))
    )
    (net (code "118") (name "unconnected-(U38-NC-Pad2)") (class "Default")
      (node (ref "U38") (pin "2") (pinfunction "NC_2") (pintype "passive+no_connect"))
    )
    (net (code "119") (name "unconnected-(U38-NC-Pad3)") (class "Default")
      (node (ref "U38") (pin "3") (pinfunction "NC_3") (pintype "passive+no_connect"))
    )
    (net (code "120") (name "unconnected-(U38-NC-Pad4)") (class "Default")
      (node (ref "U38") (pin "4") (pinfunction "NC_4") (pintype "passive+no_connect"))
    )
    (net (code "121") (name "unconnected-(U38-NC-Pad13)") (class "Default")
      (node (ref "U38") (pin "13") (pinfunction "NC_13") (pintype "passive+no_connect"))
    )
    (net (code "122") (name "unconnected-(U38-NC-Pad14)") (class "Default")
      (node (ref "U38") (pin "14") (pinfunction "NC_14") (pintype "passive+no_connect"))
    )
    (net (code "123") (name "unconnected-(U38-NC-Pad17)") (class "Default")
      (node (ref "U38") (pin "17") (pinfunction "NC_17") (pintype "passive+no_connect"))
    )
  )
)
